# design.net
KiCad netlist of a schematic drawn in Altium Designer
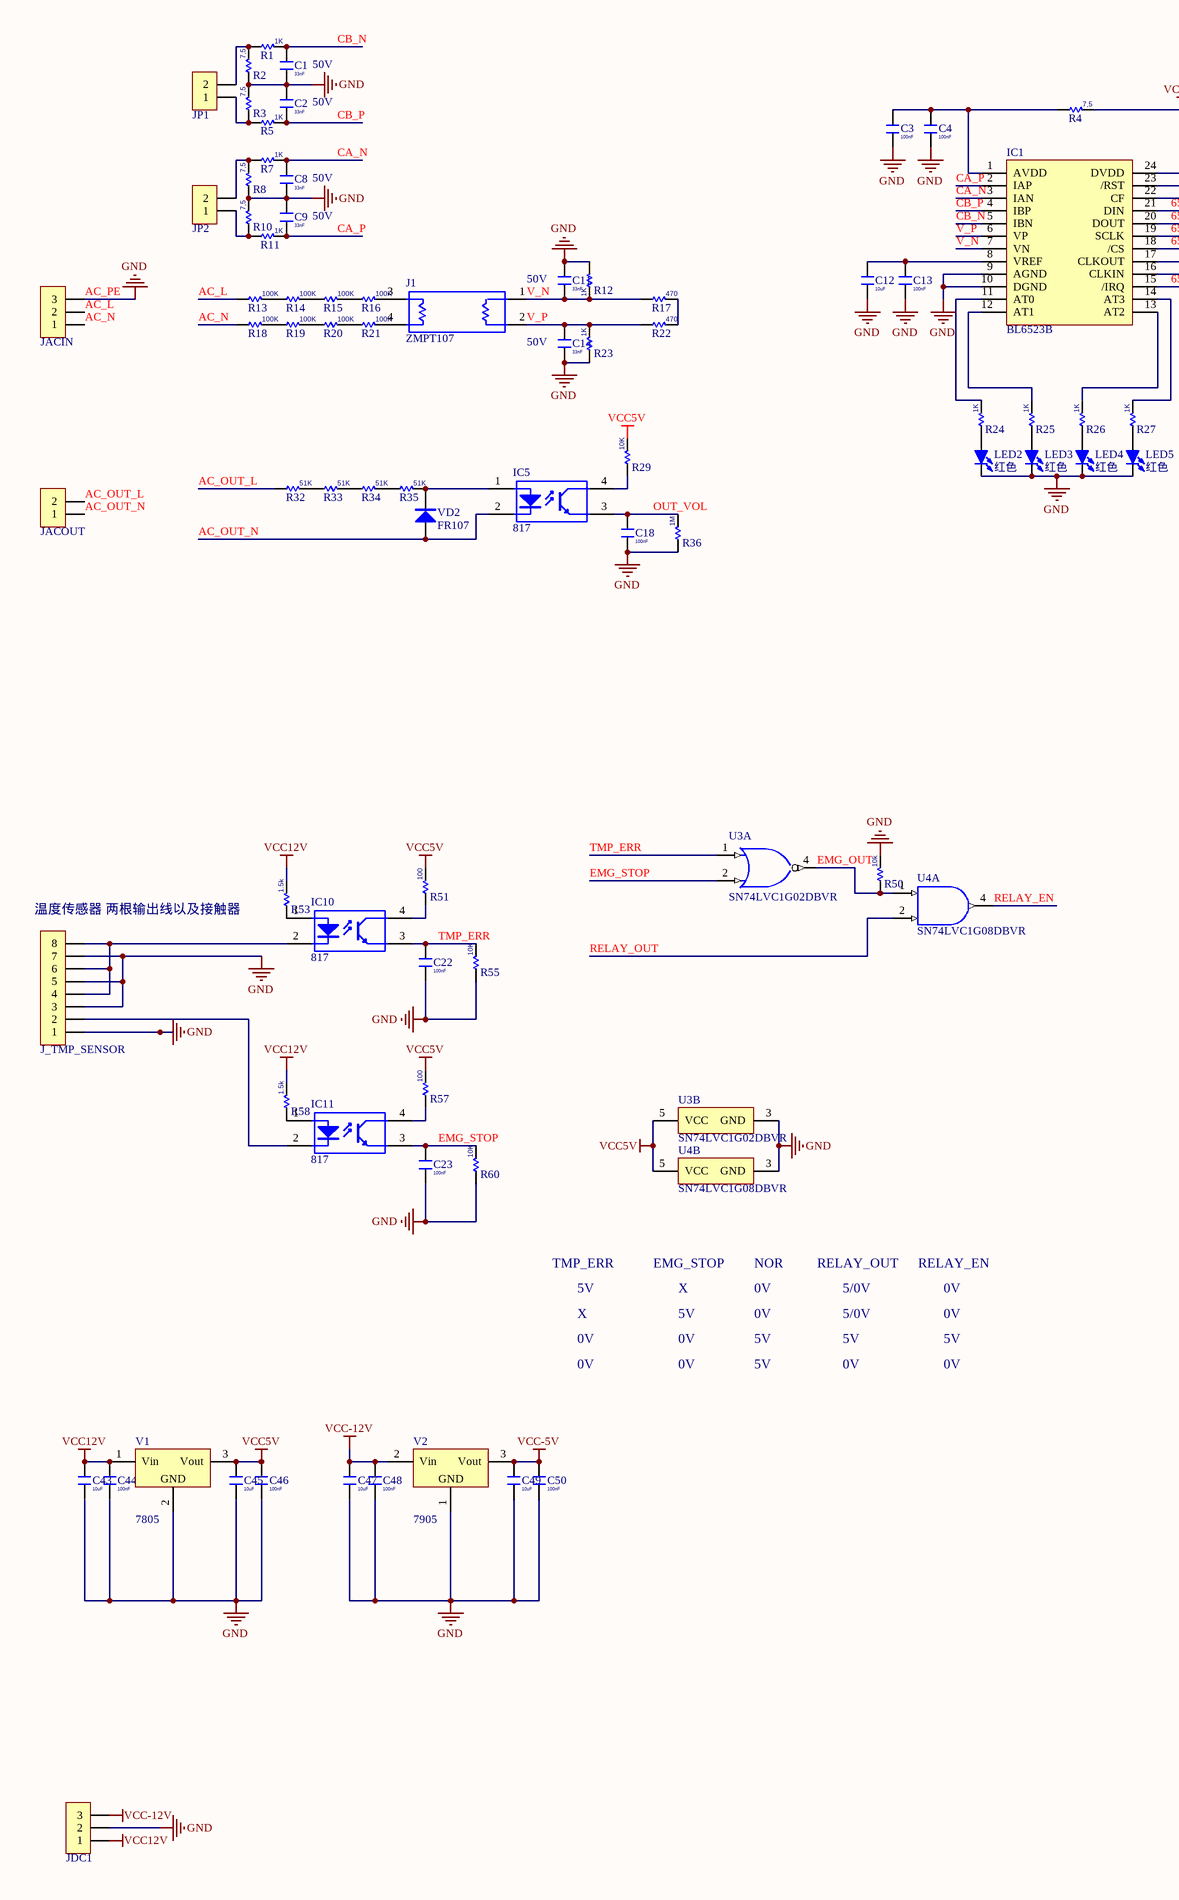
[diagram p0: 计量芯片版本.SchDoc, left]
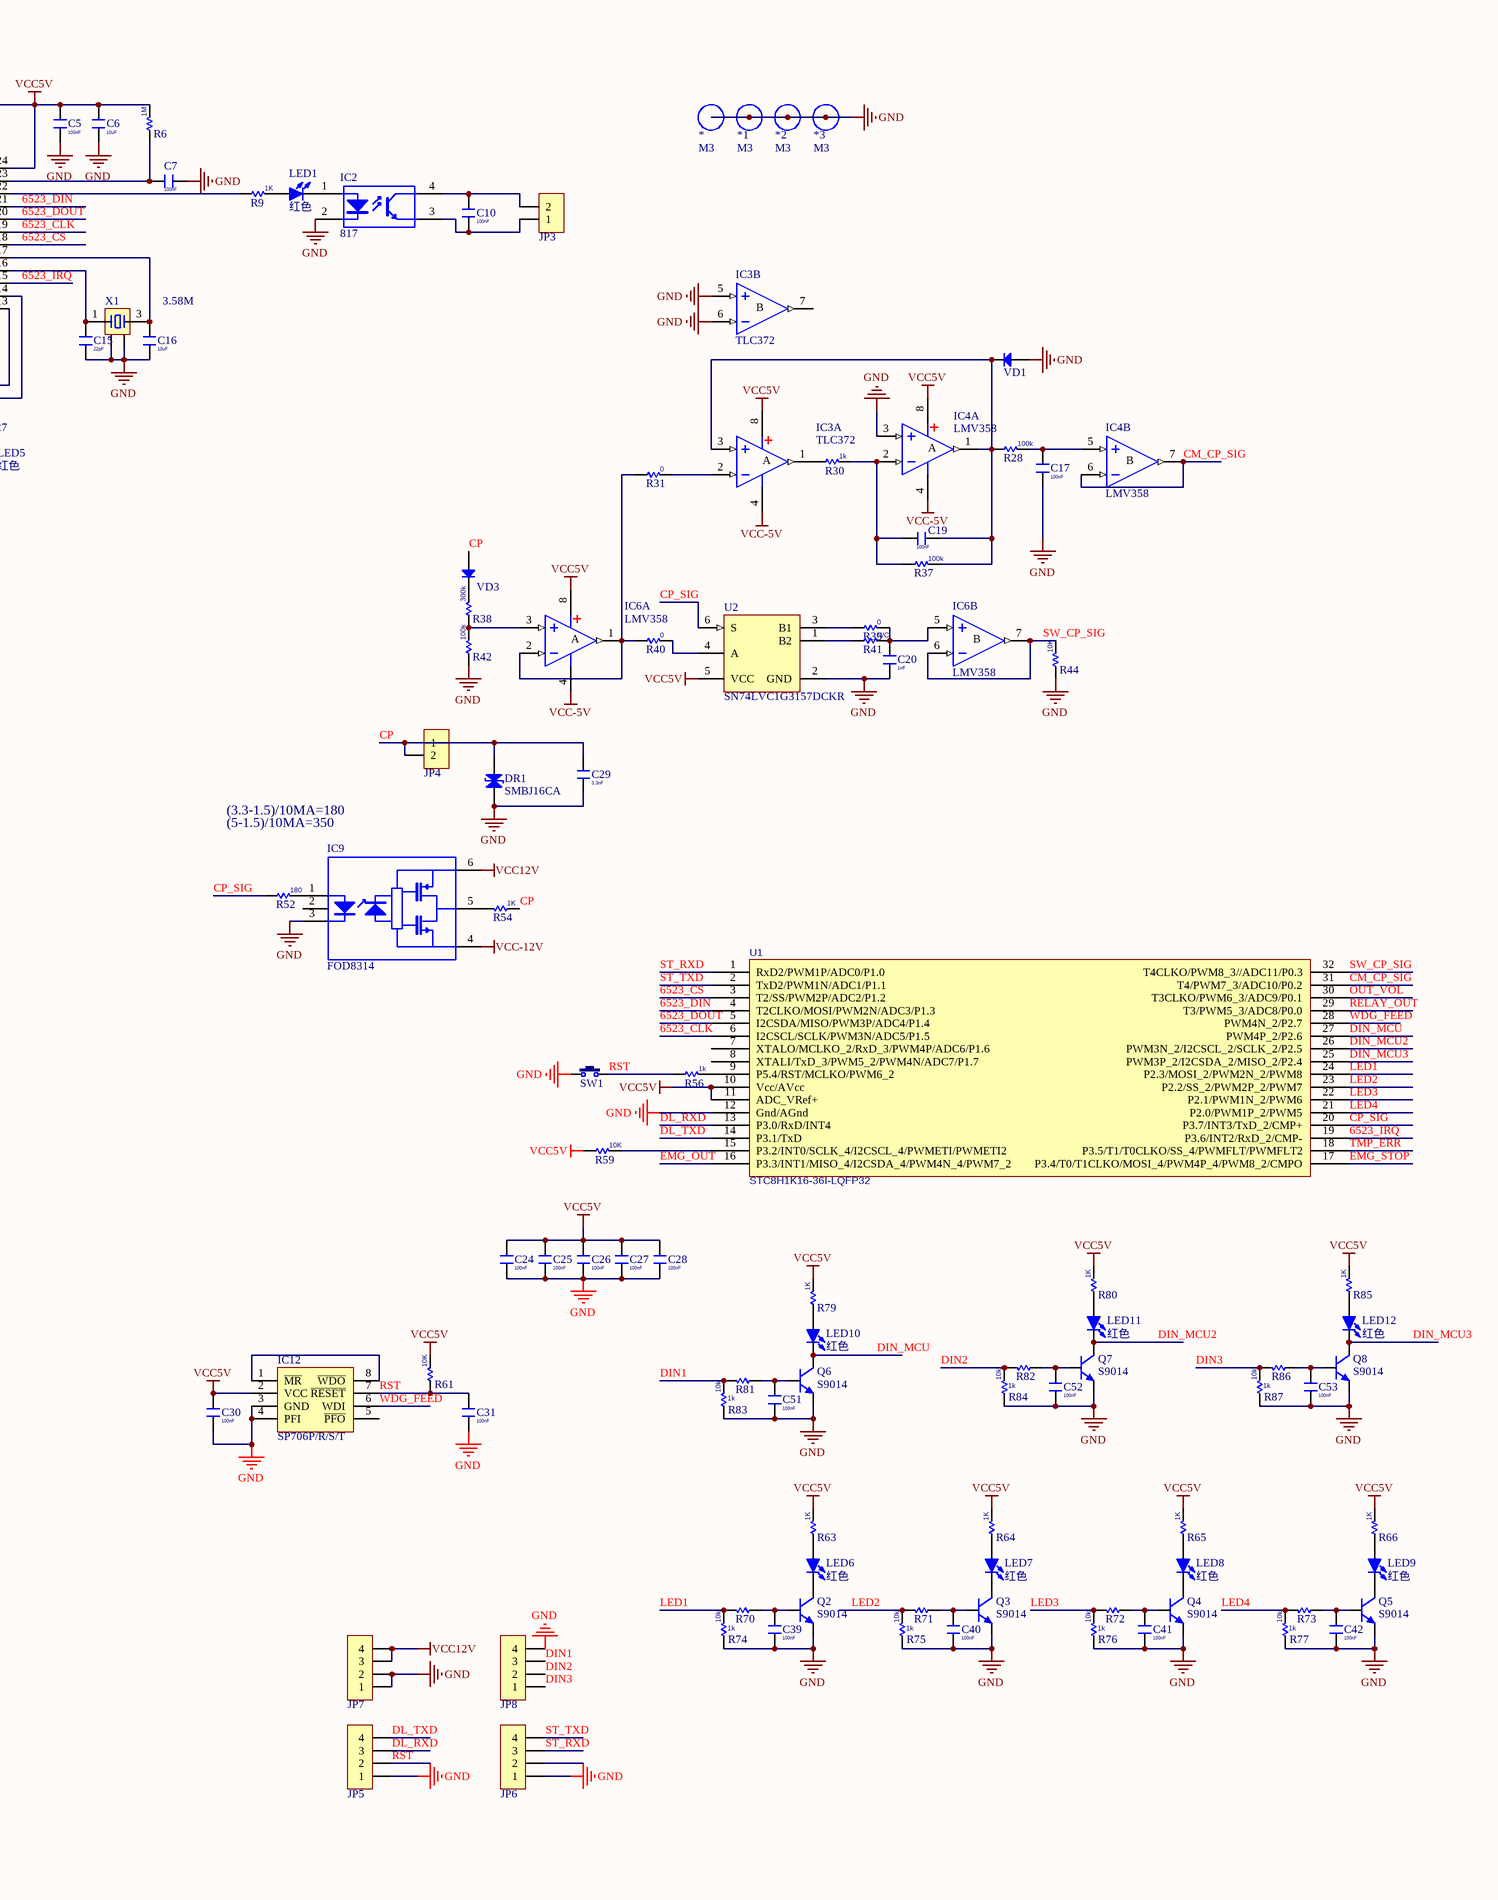
[diagram p1: 计量芯片版本.SchDoc, right]

(export (version "E")
  (design (tool "Eeschema 10.0.6"))
  (components
    (comp (ref "*")
      (value "M3")
      (footprint "M3 125X300")
      (description "铜柱孔")
      (libsource (lib "未分类器件") (part "M3"))
    )
    (comp (ref "*1")
      (value "M3")
      (footprint "M3 125X300")
      (description "铜柱孔")
      (libsource (lib "未分类器件") (part "M3"))
    )
    (comp (ref "*2")
      (value "M3")
      (footprint "M3 125X300")
      (description "铜柱孔")
      (libsource (lib "未分类器件") (part "M3"))
    )
    (comp (ref "*3")
      (value "M3")
      (footprint "M3 125X300")
      (description "铜柱孔")
      (libsource (lib "未分类器件") (part "M3"))
    )
    (comp (ref "C1")
      (value "33nF")
      (footprint "C 0805")
      (description "无极性贴片电容")
      (fields (field (name "VOLTAGE") "50V") (field (name "Comment") "C"))
      (libsource (lib "电阻-电容-电感") (part "C"))
    )
    (comp (ref "C2")
      (value "33nF")
      (footprint "C 0805")
      (description "无极性贴片电容")
      (fields (field (name "VOLTAGE") "50V") (field (name "Comment") "C"))
      (libsource (lib "电阻-电容-电感") (part "C"))
    )
    (comp (ref "C3")
      (value "100nF")
      (footprint "C 0805")
      (description "无极性贴片电容")
      (fields (field (name "VOLTAGE") "20V") (field (name "Comment") "C"))
      (libsource (lib "电阻-电容-电感") (part "C"))
    )
    (comp (ref "C4")
      (value "100nF")
      (footprint "C 0805")
      (description "无极性贴片电容")
      (fields (field (name "VOLTAGE") "20V") (field (name "Comment") "C"))
      (libsource (lib "电阻-电容-电感") (part "C"))
    )
    (comp (ref "C5")
      (value "100nF")
      (footprint "C 0805")
      (description "无极性贴片电容")
      (fields (field (name "VOLTAGE") "20V") (field (name "Comment") "C"))
      (libsource (lib "电阻-电容-电感") (part "C"))
    )
    (comp (ref "C6")
      (value "10uF")
      (footprint "C 0805")
      (description "无极性贴片电容")
      (fields (field (name "VOLTAGE") "20V") (field (name "Comment") "C"))
      (libsource (lib "电阻-电容-电感") (part "C"))
    )
    (comp (ref "C7")
      (value "100nF")
      (footprint "C 0805")
      (description "无极性贴片电容")
      (fields (field (name "VOLTAGE") "20V") (field (name "Comment") "C"))
      (libsource (lib "电阻-电容-电感") (part "C"))
    )
    (comp (ref "C8")
      (value "33nF")
      (footprint "C 0805")
      (description "无极性贴片电容")
      (fields (field (name "VOLTAGE") "50V") (field (name "Comment") "C"))
      (libsource (lib "电阻-电容-电感") (part "C"))
    )
    (comp (ref "C9")
      (value "33nF")
      (footprint "C 0805")
      (description "无极性贴片电容")
      (fields (field (name "VOLTAGE") "50V") (field (name "Comment") "C"))
      (libsource (lib "电阻-电容-电感") (part "C"))
    )
    (comp (ref "C10")
      (value "100nF")
      (footprint "C 0805")
      (description "无极性贴片电容")
      (fields (field (name "VOLTAGE") "20V") (field (name "Comment") "C"))
      (libsource (lib "电阻-电容-电感") (part "C"))
    )
    (comp (ref "C11")
      (value "33nF")
      (footprint "C 0805")
      (description "无极性贴片电容")
      (fields (field (name "VOLTAGE") "50V") (field (name "Comment") "C"))
      (libsource (lib "电阻-电容-电感") (part "C"))
    )
    (comp (ref "C12")
      (value "10uF")
      (footprint "C 0805")
      (description "无极性贴片电容")
      (fields (field (name "VOLTAGE") "20V") (field (name "Comment") "C"))
      (libsource (lib "电阻-电容-电感") (part "C"))
    )
    (comp (ref "C13")
      (value "100nF")
      (footprint "C 0805")
      (description "无极性贴片电容")
      (fields (field (name "VOLTAGE") "20V") (field (name "Comment") "C"))
      (libsource (lib "电阻-电容-电感") (part "C"))
    )
    (comp (ref "C14")
      (value "33nF")
      (footprint "C 0805")
      (description "无极性贴片电容")
      (fields (field (name "VOLTAGE") "50V") (field (name "Comment") "C"))
      (libsource (lib "电阻-电容-电感") (part "C"))
    )
    (comp (ref "C15")
      (value "22pF")
      (footprint "C 0805")
      (description "无极性贴片电容")
      (fields (field (name "VOLTAGE") "20V") (field (name "Comment") "C"))
      (libsource (lib "电阻-电容-电感") (part "C"))
    )
    (comp (ref "C16")
      (value "10uF")
      (footprint "C 0805")
      (description "无极性贴片电容")
      (fields (field (name "VOLTAGE") "20V") (field (name "Comment") "C"))
      (libsource (lib "电阻-电容-电感") (part "C"))
    )
    (comp (ref "C17")
      (value "100nF")
      (footprint "C 0805")
      (description "无极性贴片电容")
      (fields (field (name "VOLTAGE") "20V") (field (name "Comment") "C"))
      (libsource (lib "电阻-电容-电感") (part "C"))
    )
    (comp (ref "C18")
      (value "100nF")
      (footprint "C 0805")
      (description "无极性贴片电容")
      (fields (field (name "VOLTAGE") "20V") (field (name "Comment") "C"))
      (libsource (lib "电阻-电容-电感") (part "C"))
    )
    (comp (ref "C19")
      (value "100nF")
      (footprint "C 0805")
      (description "无极性贴片电容")
      (fields (field (name "VOLTAGE") "20V") (field (name "Comment") "C"))
      (libsource (lib "电阻-电容-电感") (part "C"))
    )
    (comp (ref "C20")
      (value "1nF")
      (footprint "C 0805")
      (description "无极性贴片电容")
      (fields (field (name "VOLTAGE") "20V") (field (name "Comment") "C"))
      (libsource (lib "电阻-电容-电感") (part "C"))
    )
    (comp (ref "C22")
      (value "100nF")
      (footprint "C 0805")
      (description "无极性贴片电容")
      (fields (field (name "VOLTAGE") "20V") (field (name "Comment") "C"))
      (libsource (lib "电阻-电容-电感") (part "C"))
    )
    (comp (ref "C23")
      (value "100nF")
      (footprint "C 0805")
      (description "无极性贴片电容")
      (fields (field (name "VOLTAGE") "20V") (field (name "Comment") "C"))
      (libsource (lib "电阻-电容-电感") (part "C"))
    )
    (comp (ref "C24")
      (value "100nF")
      (footprint "C 0805")
      (description "无极性贴片电容")
      (fields (field (name "VOLTAGE") "20V") (field (name "Comment") "C"))
      (libsource (lib "电阻-电容-电感") (part "C"))
    )
    (comp (ref "C25")
      (value "100nF")
      (footprint "C 0805")
      (description "无极性贴片电容")
      (fields (field (name "VOLTAGE") "20V") (field (name "Comment") "C"))
      (libsource (lib "电阻-电容-电感") (part "C"))
    )
    (comp (ref "C26")
      (value "100nF")
      (footprint "C 0805")
      (description "无极性贴片电容")
      (fields (field (name "VOLTAGE") "20V") (field (name "Comment") "C"))
      (libsource (lib "电阻-电容-电感") (part "C"))
    )
    (comp (ref "C27")
      (value "100nF")
      (footprint "C 0805")
      (description "无极性贴片电容")
      (fields (field (name "VOLTAGE") "20V") (field (name "Comment") "C"))
      (libsource (lib "电阻-电容-电感") (part "C"))
    )
    (comp (ref "C28")
      (value "100nF")
      (footprint "C 0805")
      (description "无极性贴片电容")
      (fields (field (name "VOLTAGE") "20V") (field (name "Comment") "C"))
      (libsource (lib "电阻-电容-电感") (part "C"))
    )
    (comp (ref "C29")
      (value "3.3nF")
      (footprint "C 1206")
      (description "无极性贴片电容")
      (fields (field (name "VOLTAGE") "50V") (field (name "Comment") "C"))
      (libsource (lib "电阻-电容-电感") (part "C"))
    )
    (comp (ref "C30")
      (value "100nF")
      (footprint "C 0805")
      (description "无极性贴片电容")
      (fields (field (name "VOLTAGE") "20V") (field (name "Comment") "C"))
      (libsource (lib "电阻-电容-电感") (part "C"))
    )
    (comp (ref "C31")
      (value "100nF")
      (footprint "C 0805")
      (description "无极性贴片电容")
      (fields (field (name "VOLTAGE") "20V") (field (name "Comment") "C"))
      (libsource (lib "电阻-电容-电感") (part "C"))
    )
    (comp (ref "C39")
      (value "100nF")
      (footprint "C 0805")
      (description "无极性贴片电容")
      (fields (field (name "VOLTAGE") "20V") (field (name "Comment") "C"))
      (libsource (lib "电阻-电容-电感") (part "C"))
    )
    (comp (ref "C40")
      (value "100nF")
      (footprint "C 0805")
      (description "无极性贴片电容")
      (fields (field (name "VOLTAGE") "20V") (field (name "Comment") "C"))
      (libsource (lib "电阻-电容-电感") (part "C"))
    )
    (comp (ref "C41")
      (value "100nF")
      (footprint "C 0805")
      (description "无极性贴片电容")
      (fields (field (name "VOLTAGE") "20V") (field (name "Comment") "C"))
      (libsource (lib "电阻-电容-电感") (part "C"))
    )
    (comp (ref "C42")
      (value "100nF")
      (footprint "C 0805")
      (description "无极性贴片电容")
      (fields (field (name "VOLTAGE") "20V") (field (name "Comment") "C"))
      (libsource (lib "电阻-电容-电感") (part "C"))
    )
    (comp (ref "C43")
      (value "10uF")
      (footprint "C 0805")
      (description "无极性贴片电容")
      (fields (field (name "VOLTAGE") "50V") (field (name "Comment") "C"))
      (libsource (lib "电阻-电容-电感") (part "C"))
    )
    (comp (ref "C44")
      (value "100nF")
      (footprint "C 0805")
      (description "无极性贴片电容")
      (fields (field (name "VOLTAGE") "50V") (field (name "Comment") "C"))
      (libsource (lib "电阻-电容-电感") (part "C"))
    )
    (comp (ref "C45")
      (value "10uF")
      (footprint "C 0805")
      (description "无极性贴片电容")
      (fields (field (name "VOLTAGE") "50V") (field (name "Comment") "C"))
      (libsource (lib "电阻-电容-电感") (part "C"))
    )
    (comp (ref "C46")
      (value "100nF")
      (footprint "C 0805")
      (description "无极性贴片电容")
      (fields (field (name "VOLTAGE") "50V") (field (name "Comment") "C"))
      (libsource (lib "电阻-电容-电感") (part "C"))
    )
    (comp (ref "C47")
      (value "10uF")
      (footprint "C 0805")
      (description "无极性贴片电容")
      (fields (field (name "VOLTAGE") "50V") (field (name "Comment") "C"))
      (libsource (lib "电阻-电容-电感") (part "C"))
    )
    (comp (ref "C48")
      (value "100nF")
      (footprint "C 0805")
      (description "无极性贴片电容")
      (fields (field (name "VOLTAGE") "50V") (field (name "Comment") "C"))
      (libsource (lib "电阻-电容-电感") (part "C"))
    )
    (comp (ref "C49")
      (value "10uF")
      (footprint "C 0805")
      (description "无极性贴片电容")
      (fields (field (name "VOLTAGE") "50V") (field (name "Comment") "C"))
      (libsource (lib "电阻-电容-电感") (part "C"))
    )
    (comp (ref "C50")
      (value "100nF")
      (footprint "C 0805")
      (description "无极性贴片电容")
      (fields (field (name "VOLTAGE") "50V") (field (name "Comment") "C"))
      (libsource (lib "电阻-电容-电感") (part "C"))
    )
    (comp (ref "C51")
      (value "100nF")
      (footprint "C 0805")
      (description "无极性贴片电容")
      (fields (field (name "VOLTAGE") "20V") (field (name "Comment") "C"))
      (libsource (lib "电阻-电容-电感") (part "C"))
    )
    (comp (ref "C52")
      (value "100nF")
      (footprint "C 0805")
      (description "无极性贴片电容")
      (fields (field (name "VOLTAGE") "20V") (field (name "Comment") "C"))
      (libsource (lib "电阻-电容-电感") (part "C"))
    )
    (comp (ref "C53")
      (value "100nF")
      (footprint "C 0805")
      (description "无极性贴片电容")
      (fields (field (name "VOLTAGE") "20V") (field (name "Comment") "C"))
      (libsource (lib "电阻-电容-电感") (part "C"))
    )
    (comp (ref "DR1")
      (value "SMBJ16CA")
      (footprint "SMB")
      (description "瞬态电压抑制二极管")
      (libsource (lib "二极管-整流桥") (part "DR"))
    )
    (comp (ref "IC1")
      (value "BL6523B")
      (footprint "SSOP24_M")
      (description "单相多功能电能计量芯片")
      (libsource (lib "IC芯片") (part "BL6523B"))
    )
    (comp (ref "IC2")
      (value "817")
      (footprint "DIP4-300")
      (description "线性光耦")
      (libsource (lib "传感元件") (part "817"))
    )
    (comp (ref "IC3")
      (value "TLC372")
      (footprint "SOP8_L")
      (description "双路电压比较,MOS下臂输出")
      (libsource (lib "IC芯片") (part "TLC372"))
    )
    (comp (ref "IC4")
      (value "LMV358")
      (footprint "SOP8_N")
      (description "双路运放")
      (libsource (lib "IC芯片") (part "LM358"))
    )
    (comp (ref "IC5")
      (value "817")
      (footprint "DIP4-300")
      (description "线性光耦")
      (libsource (lib "传感元件") (part "817"))
    )
    (comp (ref "IC6")
      (value "LMV358")
      (footprint "SOP8_N")
      (description "双路运放")
      (libsource (lib "IC芯片") (part "LM358"))
    )
    (comp (ref "IC9")
      (value "FOD8314")
      (footprint "SOP6_L")
      (description "MOSFET/IGBT 驱动光耦，15-30v 1a")
      (libsource (lib "传感元件") (part "FOD8314"))
    )
    (comp (ref "IC10")
      (value "817")
      (footprint "DIP4-300")
      (description "线性光耦")
      (libsource (lib "传感元件") (part "817"))
    )
    (comp (ref "IC11")
      (value "817")
      (footprint "DIP4-300")
      (description "线性光耦")
      (libsource (lib "传感元件") (part "817"))
    )
    (comp (ref "IC12")
      (value "SP706P/R/S/T")
      (footprint "SOP8_N")
      (description "处理器监控芯片")
      (libsource (lib "IC芯片") (part "SP706"))
    )
    (comp (ref "J1")
      (value "ZMPT107")
      (footprint "ZMPT107")
      (description "精密电流型电压互感器")
      (libsource (lib "传感元件") (part "ZMPT107"))
    )
    (comp (ref "JACIN")
      (value "HDR-1X3")
      (footprint "KF2EDGK5.0-3P_H")
      (description "3P接插件")
      (libsource (lib "接插件") (part "Header 3"))
    )
    (comp (ref "JACOUT")
      (value "HDR-1X2")
      (footprint "MC 1,5/ 2-G-3,81")
      (description "2P接插件")
      (libsource (lib "") (part "Header 2_2"))
    )
    (comp (ref "JDC1")
      (value "HDR-1X3")
      (footprint "MC 1,5/ 3-G-3,81")
      (description "3P接插件")
      (libsource (lib "接插件") (part "Header 3"))
    )
    (comp (ref "JP1")
      (value "HDR-1X2")
      (footprint "MC 1,5/ 2-G-3,81")
      (description "2P接插件")
      (libsource (lib "") (part "Header 2_2"))
    )
    (comp (ref "JP2")
      (value "HDR-1X2")
      (footprint "MC 1,5/ 2-G-3,81")
      (description "2P接插件")
      (libsource (lib "") (part "Header 2_2"))
    )
    (comp (ref "JP3")
      (value "HDR-1X2")
      (footprint "MC 1,5/ 2-G-3,81")
      (description "2P接插件")
      (libsource (lib "") (part "Header 2_1"))
    )
    (comp (ref "JP4")
      (value "HDR-1X2")
      (footprint "MC 1,5/ 2-G-3,81")
      (description "2P接插件")
      (libsource (lib "接插件") (part "Header 2"))
    )
    (comp (ref "JP5")
      (value "HDR-1X4")
      (footprint "HDR-1X4")
      (description "4P接插件")
      (libsource (lib "接插件") (part "Header 4"))
    )
    (comp (ref "JP6")
      (value "HDR-1X4")
      (footprint "MC 1,5/ 4-G-3,81")
      (description "4P接插件")
      (libsource (lib "接插件") (part "Header 4"))
    )
    (comp (ref "JP7")
      (value "HDR-1X4")
      (footprint "MC 1,5/ 4-G-3,81")
      (description "4P接插件")
      (libsource (lib "接插件") (part "Header 4"))
    )
    (comp (ref "JP8")
      (value "HDR-1X4")
      (footprint "MC 1,5/ 4-G-3,81")
      (description "4P接插件")
      (libsource (lib "接插件") (part "Header 4"))
    )
    (comp (ref "J_TMP_SENSOR")
      (value "HDR-1X8")
      (footprint "MC 1,5/ 8-G-3,81")
      (description "8P接插件")
      (libsource (lib "接插件") (part "Header 8"))
    )
    (comp (ref "LED1")
      (value "红色")
      (footprint "LED 0805G")
      (description "贴片LED")
      (libsource (lib "LED") (part "LED-SMD"))
    )
    (comp (ref "LED2")
      (value "红色")
      (footprint "LED 0805G")
      (description "贴片LED")
      (libsource (lib "LED") (part "LED-SMD"))
    )
    (comp (ref "LED3")
      (value "红色")
      (footprint "LED 0805G")
      (description "贴片LED")
      (libsource (lib "LED") (part "LED-SMD"))
    )
    (comp (ref "LED4")
      (value "红色")
      (footprint "LED 0805G")
      (description "贴片LED")
      (libsource (lib "LED") (part "LED-SMD"))
    )
    (comp (ref "LED5")
      (value "红色")
      (footprint "LED 0805G")
      (description "贴片LED")
      (libsource (lib "LED") (part "LED-SMD"))
    )
    (comp (ref "LED6")
      (value "红色")
      (footprint "LED 0805G")
      (description "贴片LED")
      (libsource (lib "LED") (part "LED-SMD"))
    )
    (comp (ref "LED7")
      (value "红色")
      (footprint "LED 0805G")
      (description "贴片LED")
      (libsource (lib "LED") (part "LED-SMD"))
    )
    (comp (ref "LED8")
      (value "红色")
      (footprint "LED 0805G")
      (description "贴片LED")
      (libsource (lib "LED") (part "LED-SMD"))
    )
    (comp (ref "LED9")
      (value "红色")
      (footprint "LED 0805G")
      (description "贴片LED")
      (libsource (lib "LED") (part "LED-SMD"))
    )
    (comp (ref "LED10")
      (value "红色")
      (footprint "LED 0805G")
      (description "贴片LED")
      (libsource (lib "LED") (part "LED-SMD"))
    )
    (comp (ref "LED11")
      (value "红色")
      (footprint "LED 0805G")
      (description "贴片LED")
      (libsource (lib "LED") (part "LED-SMD"))
    )
    (comp (ref "LED12")
      (value "红色")
      (footprint "LED 0805G")
      (description "贴片LED")
      (libsource (lib "LED") (part "LED-SMD"))
    )
    (comp (ref "Q2")
      (value "S9014")
      (footprint "SOT23-3N")
      (description "低噪放大-NPN型")
      (libsource (lib "三极管") (part "9014-SMD"))
    )
    (comp (ref "Q3")
      (value "S9014")
      (footprint "SOT23-3N")
      (description "低噪放大-NPN型")
      (libsource (lib "三极管") (part "9014-SMD"))
    )
    (comp (ref "Q4")
      (value "S9014")
      (footprint "SOT23-3N")
      (description "低噪放大-NPN型")
      (libsource (lib "三极管") (part "9014-SMD"))
    )
    (comp (ref "Q5")
      (value "S9014")
      (footprint "SOT23-3N")
      (description "低噪放大-NPN型")
      (libsource (lib "三极管") (part "9014-SMD"))
    )
    (comp (ref "Q6")
      (value "S9014")
      (footprint "SOT23-3N")
      (description "低噪放大-NPN型")
      (libsource (lib "三极管") (part "9014-SMD"))
    )
    (comp (ref "Q7")
      (value "S9014")
      (footprint "SOT23-3N")
      (description "低噪放大-NPN型")
      (libsource (lib "三极管") (part "9014-SMD"))
    )
    (comp (ref "Q8")
      (value "S9014")
      (footprint "SOT23-3N")
      (description "低噪放大-NPN型")
      (libsource (lib "三极管") (part "9014-SMD"))
    )
    (comp (ref "R1")
      (value "1K")
      (footprint "R 0805")
      (description "贴片电阻")
      (fields (field (name "Comment") "R"))
      (libsource (lib "电阻-电容-电感") (part "R"))
    )
    (comp (ref "R2")
      (value "7,5")
      (footprint "R 0805")
      (description "贴片电阻")
      (fields (field (name "Comment") "R"))
      (libsource (lib "电阻-电容-电感") (part "R"))
    )
    (comp (ref "R3")
      (value "7,5")
      (footprint "R 0805")
      (description "贴片电阻")
      (fields (field (name "Comment") "R"))
      (libsource (lib "电阻-电容-电感") (part "R"))
    )
    (comp (ref "R4")
      (value "7,5")
      (footprint "R 0805")
      (description "贴片电阻")
      (fields (field (name "Comment") "R"))
      (libsource (lib "电阻-电容-电感") (part "R"))
    )
    (comp (ref "R5")
      (value "1K")
      (footprint "R 0805")
      (description "贴片电阻")
      (fields (field (name "Comment") "R"))
      (libsource (lib "电阻-电容-电感") (part "R"))
    )
    (comp (ref "R6")
      (value "1M")
      (footprint "R 0805")
      (description "贴片电阻")
      (fields (field (name "Comment") "R"))
      (libsource (lib "电阻-电容-电感") (part "R"))
    )
    (comp (ref "R7")
      (value "1K")
      (footprint "R 0805")
      (description "贴片电阻")
      (fields (field (name "Comment") "R"))
      (libsource (lib "电阻-电容-电感") (part "R"))
    )
    (comp (ref "R8")
      (value "7,5")
      (footprint "R 0805")
      (description "贴片电阻")
      (fields (field (name "Comment") "R"))
      (libsource (lib "电阻-电容-电感") (part "R"))
    )
    (comp (ref "R9")
      (value "1K")
      (footprint "R 0805")
      (description "贴片电阻")
      (fields (field (name "Comment") "R"))
      (libsource (lib "电阻-电容-电感") (part "R"))
    )
    (comp (ref "R10")
      (value "7,5")
      (footprint "R 0805")
      (description "贴片电阻")
      (fields (field (name "Comment") "R"))
      (libsource (lib "电阻-电容-电感") (part "R"))
    )
    (comp (ref "R11")
      (value "1K")
      (footprint "R 0805")
      (description "贴片电阻")
      (fields (field (name "Comment") "R"))
      (libsource (lib "电阻-电容-电感") (part "R"))
    )
    (comp (ref "R12")
      (value "1K")
      (footprint "R 0805")
      (description "贴片电阻")
      (fields (field (name "Comment") "R"))
      (libsource (lib "电阻-电容-电感") (part "R"))
    )
    (comp (ref "R13")
      (value "100K")
      (footprint "R 1206")
      (description "贴片电阻")
      (fields (field (name "Comment") "R"))
      (libsource (lib "电阻-电容-电感") (part "R"))
    )
    (comp (ref "R14")
      (value "100K")
      (footprint "R 1206")
      (description "贴片电阻")
      (fields (field (name "Comment") "R"))
      (libsource (lib "电阻-电容-电感") (part "R"))
    )
    (comp (ref "R15")
      (value "100K")
      (footprint "R 1206")
      (description "贴片电阻")
      (fields (field (name "Comment") "R"))
      (libsource (lib "电阻-电容-电感") (part "R"))
    )
    (comp (ref "R16")
      (value "100K")
      (footprint "R 1206")
      (description "贴片电阻")
      (fields (field (name "Comment") "R"))
      (libsource (lib "电阻-电容-电感") (part "R"))
    )
    (comp (ref "R17")
      (value "470")
      (footprint "R 0805")
      (description "贴片电阻")
      (fields (field (name "Comment") "R"))
      (libsource (lib "电阻-电容-电感") (part "R"))
    )
    (comp (ref "R18")
      (value "100K")
      (footprint "R 1206")
      (description "贴片电阻")
      (fields (field (name "Comment") "R"))
      (libsource (lib "电阻-电容-电感") (part "R"))
    )
    (comp (ref "R19")
      (value "100K")
      (footprint "R 1206")
      (description "贴片电阻")
      (fields (field (name "Comment") "R"))
      (libsource (lib "电阻-电容-电感") (part "R"))
    )
    (comp (ref "R20")
      (value "100K")
      (footprint "R 1206")
      (description "贴片电阻")
      (fields (field (name "Comment") "R"))
      (libsource (lib "电阻-电容-电感") (part "R"))
    )
    (comp (ref "R21")
      (value "100K")
      (footprint "R 1206")
      (description "贴片电阻")
      (fields (field (name "Comment") "R"))
      (libsource (lib "电阻-电容-电感") (part "R"))
    )
    (comp (ref "R22")
      (value "470")
      (footprint "R 0805")
      (description "贴片电阻")
      (fields (field (name "Comment") "R"))
      (libsource (lib "电阻-电容-电感") (part "R"))
    )
    (comp (ref "R23")
      (value "1K")
      (footprint "R 0805")
      (description "贴片电阻")
      (fields (field (name "Comment") "R"))
      (libsource (lib "电阻-电容-电感") (part "R"))
    )
    (comp (ref "R24")
      (value "1K")
      (footprint "R 0805")
      (description "贴片电阻")
      (fields (field (name "Comment") "R"))
      (libsource (lib "电阻-电容-电感") (part "R"))
    )
    (comp (ref "R25")
      (value "1K")
      (footprint "R 0805")
      (description "贴片电阻")
      (fields (field (name "Comment") "R"))
      (libsource (lib "电阻-电容-电感") (part "R"))
    )
    (comp (ref "R26")
      (value "1K")
      (footprint "R 0805")
      (description "贴片电阻")
      (fields (field (name "Comment") "R"))
      (libsource (lib "电阻-电容-电感") (part "R"))
    )
    (comp (ref "R27")
      (value "1K")
      (footprint "R 0805")
      (description "贴片电阻")
      (fields (field (name "Comment") "R"))
      (libsource (lib "电阻-电容-电感") (part "R"))
    )
    (comp (ref "R28")
      (value "100k")
      (footprint "R 0805")
      (description "贴片电阻")
      (fields (field (name "Comment") "R"))
      (libsource (lib "电阻-电容-电感") (part "R"))
    )
    (comp (ref "R29")
      (value "10K")
      (footprint "R 0805")
      (description "贴片电阻")
      (fields (field (name "Comment") "R"))
      (libsource (lib "电阻-电容-电感") (part "R"))
    )
    (comp (ref "R30")
      (value "1k")
      (footprint "R 0805")
      (description "贴片电阻")
      (fields (field (name "Comment") "R"))
      (libsource (lib "电阻-电容-电感") (part "R"))
    )
    (comp (ref "R31")
      (value "0")
      (footprint "R 0805")
      (description "贴片电阻")
      (fields (field (name "Comment") "R"))
      (libsource (lib "电阻-电容-电感") (part "R"))
    )
    (comp (ref "R32")
      (value "51K")
      (footprint "R 1206")
      (description "贴片电阻")
      (fields (field (name "Comment") "R"))
      (libsource (lib "电阻-电容-电感") (part "R"))
    )
    (comp (ref "R33")
      (value "51K")
      (footprint "R 1206")
      (description "贴片电阻")
      (fields (field (name "Comment") "R"))
      (libsource (lib "电阻-电容-电感") (part "R"))
    )
    (comp (ref "R34")
      (value "51K")
      (footprint "R 1206")
      (description "贴片电阻")
      (fields (field (name "Comment") "R"))
      (libsource (lib "电阻-电容-电感") (part "R"))
    )
    (comp (ref "R35")
      (value "51K")
      (footprint "R 1206")
      (description "贴片电阻")
      (fields (field (name "Comment") "R"))
      (libsource (lib "电阻-电容-电感") (part "R"))
    )
    (comp (ref "R36")
      (value "1M")
      (footprint "R 0805")
      (description "贴片电阻")
      (fields (field (name "Comment") "R"))
      (libsource (lib "电阻-电容-电感") (part "R"))
    )
    (comp (ref "R37")
      (value "100k")
      (footprint "R 0805")
      (description "贴片电阻")
      (fields (field (name "Comment") "R"))
      (libsource (lib "电阻-电容-电感") (part "R"))
    )
    (comp (ref "R38")
      (value "300k")
      (footprint "R 0805")
      (description "贴片电阻")
      (fields (field (name "Comment") "R"))
      (libsource (lib "电阻-电容-电感") (part "R"))
    )
    (comp (ref "R39")
      (value "0")
      (footprint "R 0805")
      (description "贴片电阻")
      (fields (field (name "Comment") "R"))
      (libsource (lib "电阻-电容-电感") (part "R"))
    )
    (comp (ref "R40")
      (value "0")
      (footprint "R 0805")
      (description "贴片电阻")
      (fields (field (name "Comment") "R"))
      (libsource (lib "电阻-电容-电感") (part "R"))
    )
    (comp (ref "R41")
      (value "N/C")
      (footprint "R 0805")
      (description "贴片电阻")
      (fields (field (name "Comment") "R"))
      (libsource (lib "电阻-电容-电感") (part "R"))
    )
    (comp (ref "R42")
      (value "100k")
      (footprint "R 0805")
      (description "贴片电阻")
      (fields (field (name "Comment") "R"))
      (libsource (lib "电阻-电容-电感") (part "R"))
    )
    (comp (ref "R44")
      (value "10K")
      (footprint "R 0805")
      (description "贴片电阻")
      (fields (field (name "Comment") "R"))
      (libsource (lib "电阻-电容-电感") (part "R"))
    )
    (comp (ref "R50")
      (value "10k")
      (footprint "R 0805")
      (description "贴片电阻")
      (fields (field (name "Comment") "R"))
      (libsource (lib "电阻-电容-电感") (part "R"))
    )
    (comp (ref "R51")
      (value "100")
      (footprint "R 0805")
      (description "贴片电阻")
      (fields (field (name "Comment") "R"))
      (libsource (lib "电阻-电容-电感") (part "R"))
    )
    (comp (ref "R52")
      (value "180")
      (footprint "R 0805")
      (description "贴片电阻")
      (fields (field (name "Comment") "R"))
      (libsource (lib "电阻-电容-电感") (part "R"))
    )
    (comp (ref "R53")
      (value "1.5k")
      (footprint "R 0805")
      (description "贴片电阻")
      (fields (field (name "Comment") "R"))
      (libsource (lib "电阻-电容-电感") (part "R"))
    )
    (comp (ref "R54")
      (value "1K")
      (footprint "R 1206")
      (description "贴片电阻")
      (fields (field (name "Comment") "R"))
      (libsource (lib "电阻-电容-电感") (part "R"))
    )
    (comp (ref "R55")
      (value "10K")
      (footprint "R 0805")
      (description "贴片电阻")
      (fields (field (name "Comment") "R"))
      (libsource (lib "电阻-电容-电感") (part "R"))
    )
    (comp (ref "R56")
      (value "1k")
      (footprint "R 0805")
      (description "贴片电阻")
      (fields (field (name "Comment") "R"))
      (libsource (lib "电阻-电容-电感") (part "R"))
    )
    (comp (ref "R57")
      (value "100")
      (footprint "R 0805")
      (description "贴片电阻")
      (fields (field (name "Comment") "R"))
      (libsource (lib "电阻-电容-电感") (part "R"))
    )
    (comp (ref "R58")
      (value "1.5k")
      (footprint "R 0805")
      (description "贴片电阻")
      (fields (field (name "Comment") "R"))
      (libsource (lib "电阻-电容-电感") (part "R"))
    )
    (comp (ref "R59")
      (value "10K")
      (footprint "R 0805")
      (description "贴片电阻")
      (fields (field (name "Comment") "R"))
      (libsource (lib "电阻-电容-电感") (part "R"))
    )
    (comp (ref "R60")
      (value "10K")
      (footprint "R 0805")
      (description "贴片电阻")
      (fields (field (name "Comment") "R"))
      (libsource (lib "电阻-电容-电感") (part "R"))
    )
    (comp (ref "R61")
      (value "10K")
      (footprint "R 0805")
      (description "贴片电阻")
      (fields (field (name "Comment") "R"))
      (libsource (lib "电阻-电容-电感") (part "R"))
    )
    (comp (ref "R63")
      (value "1K")
      (footprint "R 0805")
      (description "贴片电阻")
      (fields (field (name "Comment") "R"))
      (libsource (lib "电阻-电容-电感") (part "R"))
    )
    (comp (ref "R64")
      (value "1K")
      (footprint "R 0805")
      (description "贴片电阻")
      (fields (field (name "Comment") "R"))
      (libsource (lib "电阻-电容-电感") (part "R"))
    )
    (comp (ref "R65")
      (value "1K")
      (footprint "R 0805")
      (description "贴片电阻")
      (fields (field (name "Comment") "R"))
      (libsource (lib "电阻-电容-电感") (part "R"))
    )
    (comp (ref "R66")
      (value "1K")
      (footprint "R 0805")
      (description "贴片电阻")
      (fields (field (name "Comment") "R"))
      (libsource (lib "电阻-电容-电感") (part "R"))
    )
    (comp (ref "R70")
      (value "1k")
      (footprint "R 0805")
      (description "贴片电阻")
      (fields (field (name "Comment") "R"))
      (libsource (lib "电阻-电容-电感") (part "R"))
    )
    (comp (ref "R71")
      (value "1k")
      (footprint "R 0805")
      (description "贴片电阻")
      (fields (field (name "Comment") "R"))
      (libsource (lib "电阻-电容-电感") (part "R"))
    )
    (comp (ref "R72")
      (value "1k")
      (footprint "R 0805")
      (description "贴片电阻")
      (fields (field (name "Comment") "R"))
      (libsource (lib "电阻-电容-电感") (part "R"))
    )
    (comp (ref "R73")
      (value "1k")
      (footprint "R 0805")
      (description "贴片电阻")
      (fields (field (name "Comment") "R"))
      (libsource (lib "电阻-电容-电感") (part "R"))
    )
    (comp (ref "R74")
      (value "10k")
      (footprint "R 0805")
      (description "贴片电阻")
      (fields (field (name "Comment") "R"))
      (libsource (lib "电阻-电容-电感") (part "R"))
    )
    (comp (ref "R75")
      (value "10k")
      (footprint "R 0805")
      (description "贴片电阻")
      (fields (field (name "Comment") "R"))
      (libsource (lib "电阻-电容-电感") (part "R"))
    )
    (comp (ref "R76")
      (value "10k")
      (footprint "R 0805")
      (description "贴片电阻")
      (fields (field (name "Comment") "R"))
      (libsource (lib "电阻-电容-电感") (part "R"))
    )
    (comp (ref "R77")
      (value "10k")
      (footprint "R 0805")
      (description "贴片电阻")
      (fields (field (name "Comment") "R"))
      (libsource (lib "电阻-电容-电感") (part "R"))
    )
    (comp (ref "R79")
      (value "1K")
      (footprint "R 0805")
      (description "贴片电阻")
      (fields (field (name "Comment") "R"))
      (libsource (lib "电阻-电容-电感") (part "R"))
    )
    (comp (ref "R80")
      (value "1K")
      (footprint "R 0805")
      (description "贴片电阻")
      (fields (field (name "Comment") "R"))
      (libsource (lib "电阻-电容-电感") (part "R"))
    )
    (comp (ref "R81")
      (value "1k")
      (footprint "R 0805")
      (description "贴片电阻")
      (fields (field (name "Comment") "R"))
      (libsource (lib "电阻-电容-电感") (part "R"))
    )
    (comp (ref "R82")
      (value "1k")
      (footprint "R 0805")
      (description "贴片电阻")
      (fields (field (name "Comment") "R"))
      (libsource (lib "电阻-电容-电感") (part "R"))
    )
    (comp (ref "R83")
      (value "10k")
      (footprint "R 0805")
      (description "贴片电阻")
      (fields (field (name "Comment") "R"))
      (libsource (lib "电阻-电容-电感") (part "R"))
    )
    (comp (ref "R84")
      (value "10k")
      (footprint "R 0805")
      (description "贴片电阻")
      (fields (field (name "Comment") "R"))
      (libsource (lib "电阻-电容-电感") (part "R"))
    )
    (comp (ref "R85")
      (value "1K")
      (footprint "R 0805")
      (description "贴片电阻")
      (fields (field (name "Comment") "R"))
      (libsource (lib "电阻-电容-电感") (part "R"))
    )
    (comp (ref "R86")
      (value "1k")
      (footprint "R 0805")
      (description "贴片电阻")
      (fields (field (name "Comment") "R"))
      (libsource (lib "电阻-电容-电感") (part "R"))
    )
    (comp (ref "R87")
      (value "10k")
      (footprint "R 0805")
      (description "贴片电阻")
      (fields (field (name "Comment") "R"))
      (libsource (lib "电阻-电容-电感") (part "R"))
    )
    (comp (ref "SW1") (value "NC") (footprint "HDR-1x2") (libsource (lib "按键-开关") (part "TSW 3x6")))
    (comp (ref "U1")
      (value "STC8H1K16-36I-LQFP32")
      (footprint "LQFP32 7X7_N")
      (libsource (lib "STC系列单片机") (part "STC8H1K16-36I-LQFP32"))
    )
    (comp (ref "U2")
      (value "SN74LVC1G3157DCKR")
      (footprint "DCK0006A_N")
      (description "Single-Pole, Double-Throw Analog Switch, DCK0006A, LARGE T&R")
      (fields
        (field (name "GENERIC PART NUMBER") "SN74LVC1G3157")
        (field (name "MANUFACTURER") "Texas Instruments")
      )
      (libsource (lib "TI_Logic_Little_Logic") (part "SN74LVC1G3157DCKR"))
    )
    (comp (ref "U3")
      (value "SN74LVC1G02DBVR")
      (footprint "DBV0005A_N")
      (description "Single 2-Input Positive-NOR Gate, DBV0005A, LARGE T&R")
      (fields
        (field (name "GENERIC PART NUMBER") "SN74LVC1G02")
        (field (name "MANUFACTURER") "Texas Instruments")
      )
      (libsource (lib "TI_Logic_Little_Logic") (part "SN74LVC1G02DBVR"))
    )
    (comp (ref "U4")
      (value "SN74LVC1G08DBVR")
      (footprint "DBV0005A_N")
      (description "Single 2-Input Positive-AND Gate, DBV0005A, LARGE T&R")
      (fields
        (field (name "GENERIC PART NUMBER") "SN74LVC1G08")
        (field (name "MANUFACTURER") "Texas Instruments")
      )
      (libsource (lib "TI_Logic_Little_Logic") (part "SN74LVC1G08DBVR"))
    )
    (comp (ref "V1")
      (value "7805")
      (footprint "TO252")
      (description "线性稳压芯片")
      (libsource (lib "IC芯片") (part "78xx"))
    )
    (comp (ref "V2")
      (value "7905")
      (footprint "TO252")
      (description "线性稳压芯片")
      (libsource (lib "IC芯片") (part "79xx"))
    )
    (comp (ref "VD1")
      (value "1N4148")
      (footprint "SOD-323")
      (description "高速开关二极管")
      (libsource (lib "二极管-整流桥") (part "1N4148"))
    )
    (comp (ref "VD2")
      (value "FR107")
      (footprint "SOD-123")
      (description "快恢复整流二极管")
      (libsource (lib "二极管-整流桥") (part "FR107"))
    )
    (comp (ref "VD3")
      (value "1N4148")
      (footprint "SOD-323")
      (description "高速开关二极管")
      (libsource (lib "二极管-整流桥") (part "1N4148"))
    )
    (comp (ref "X1")
      (value "3.58M")
      (footprint "XTAL-3225")
      (description "4脚晶振")
      (libsource (lib "保险丝-晶振") (part "XTAL-4"))
    )
  )
  (nets
    (net (code "1") (name "/6523_CLK") (class "Default")
      (node (ref "IC1") (pin "19") (pinfunction "SCLK_19") (pintype "passive"))
      (node (ref "U1") (pin "6") (pinfunction "I2CSCL/SCLK/PWM3N/ADC5/P1.5_6") (pintype "passive"))
    )
    (net (code "2") (name "/6523_CS") (class "Default")
      (node (ref "IC1") (pin "18") (pinfunction "/CS_18") (pintype "passive"))
      (node (ref "U1") (pin "3") (pinfunction "T2/SS/PWM2P/ADC2/P1.2_3") (pintype "passive"))
    )
    (net (code "3") (name "/6523_DIN") (class "Default")
      (node (ref "IC1") (pin "21") (pinfunction "DIN_21") (pintype "passive"))
      (node (ref "U1") (pin "4") (pinfunction "T2CLKO/MOSI/PWM2N/ADC3/P1.3_4") (pintype "passive"))
    )
    (net (code "4") (name "/6523_DOUT") (class "Default")
      (node (ref "IC1") (pin "20") (pinfunction "DOUT_20") (pintype "passive"))
      (node (ref "U1") (pin "5") (pinfunction "I2CSDA/MISO/PWM3P/ADC4/P1.4_5") (pintype "passive"))
    )
    (net (code "5") (name "/6523_IRQ") (class "Default")
      (node (ref "IC1") (pin "15") (pinfunction "/IRQ_15") (pintype "passive"))
      (node (ref "U1") (pin "19") (pinfunction "P3.6/INT2/RxD_2/CMP-_19") (pintype "passive"))
    )
    (net (code "6") (name "/AC_L") (class "Default")
      (node (ref "JACIN") (pin "2") (pinfunction "2_2") (pintype "passive"))
      (node (ref "R13") (pin "1") (pinfunction "1_1") (pintype "passive"))
    )
    (net (code "7") (name "/AC_N") (class "Default")
      (node (ref "JACIN") (pin "1") (pinfunction "1_1") (pintype "passive"))
      (node (ref "R18") (pin "1") (pinfunction "1_1") (pintype "passive"))
    )
    (net (code "8") (name "/AC_OUT_L") (class "Default")
      (node (ref "JACOUT") (pin "2") (pinfunction "2_2") (pintype "passive"))
      (node (ref "R32") (pin "1") (pinfunction "1_1") (pintype "passive"))
    )
    (net (code "9") (name "/AC_OUT_N") (class "Default")
      (node (ref "IC5") (pin "2") (pinfunction "K_2") (pintype "passive"))
      (node (ref "JACOUT") (pin "1") (pinfunction "1_1") (pintype "passive"))
      (node (ref "VD2") (pin "1") (pinfunction "A_1") (pintype "passive"))
    )
    (net (code "10") (name "/CA_N") (class "Default")
      (node (ref "C8") (pin "2") (pinfunction "2_2") (pintype "passive"))
      (node (ref "IC1") (pin "3") (pinfunction "IAN_3") (pintype "passive"))
      (node (ref "R7") (pin "2") (pinfunction "2_2") (pintype "passive"))
    )
    (net (code "11") (name "/CA_P") (class "Default")
      (node (ref "C9") (pin "1") (pinfunction "1_1") (pintype "passive"))
      (node (ref "IC1") (pin "2") (pinfunction "IAP_2") (pintype "passive"))
      (node (ref "R11") (pin "2") (pinfunction "2_2") (pintype "passive"))
    )
    (net (code "12") (name "/CB_N") (class "Default")
      (node (ref "C1") (pin "2") (pinfunction "2_2") (pintype "passive"))
      (node (ref "IC1") (pin "5") (pinfunction "IBN_5") (pintype "passive"))
      (node (ref "R1") (pin "2") (pinfunction "2_2") (pintype "passive"))
    )
    (net (code "13") (name "/CB_P") (class "Default")
      (node (ref "C2") (pin "1") (pinfunction "1_1") (pintype "passive"))
      (node (ref "IC1") (pin "4") (pinfunction "IBP_4") (pintype "passive"))
      (node (ref "R5") (pin "2") (pinfunction "2_2") (pintype "passive"))
    )
    (net (code "14") (name "/CM_CP_SIG") (class "Default")
      (node (ref "IC4") (pin "6") (pinfunction "IN-_6") (pintype "input"))
      (node (ref "IC4") (pin "7") (pinfunction "OUT_7") (pintype "output"))
      (node (ref "U1") (pin "31") (pinfunction "T4/PWM7_3/ADC10/P0.2_31") (pintype "passive"))
    )
    (net (code "15") (name "/CP") (class "Default")
      (node (ref "C29") (pin "2") (pinfunction "2_2") (pintype "passive"))
      (node (ref "DR1") (pin "1") (pinfunction "A_1") (pintype "passive"))
      (node (ref "JP4") (pin "1") (pinfunction "1_1") (pintype "passive"))
      (node (ref "JP4") (pin "2") (pinfunction "2_2") (pintype "passive"))
      (node (ref "R54") (pin "1") (pinfunction "1_1") (pintype "passive"))
      (node (ref "VD3") (pin "1") (pinfunction "A_1") (pintype "passive"))
    )
    (net (code "16") (name "/CP_SIG") (class "Default")
      (node (ref "R52") (pin "1") (pinfunction "1_1") (pintype "passive"))
      (node (ref "U1") (pin "20") (pinfunction "P3.7/INT3/TxD_2/CMP+_20") (pintype "passive"))
      (node (ref "U2") (pin "6") (pinfunction "S_6") (pintype "input"))
    )
    (net (code "17") (name "/DIN1") (class "Default")
      (node (ref "JP8") (pin "3") (pinfunction "3_3") (pintype "passive"))
      (node (ref "R81") (pin "2") (pinfunction "2_2") (pintype "passive"))
      (node (ref "R83") (pin "2") (pinfunction "2_2") (pintype "passive"))
    )
    (net (code "18") (name "/DIN2") (class "Default")
      (node (ref "JP8") (pin "2") (pinfunction "2_2") (pintype "passive"))
      (node (ref "R82") (pin "2") (pinfunction "2_2") (pintype "passive"))
      (node (ref "R84") (pin "2") (pinfunction "2_2") (pintype "passive"))
    )
    (net (code "19") (name "/DIN3") (class "Default")
      (node (ref "JP8") (pin "1") (pinfunction "1_1") (pintype "passive"))
      (node (ref "R86") (pin "2") (pinfunction "2_2") (pintype "passive"))
      (node (ref "R87") (pin "2") (pinfunction "2_2") (pintype "passive"))
    )
    (net (code "20") (name "/DIN_MCU") (class "Default")
      (node (ref "LED10") (pin "2") (pinfunction "K_2") (pintype "passive"))
      (node (ref "Q6") (pin "3") (pinfunction "C_3") (pintype "passive"))
      (node (ref "U1") (pin "27") (pinfunction "PWM4P_2/P2.6_27") (pintype "passive"))
    )
    (net (code "21") (name "/DIN_MCU2") (class "Default")
      (node (ref "LED11") (pin "2") (pinfunction "K_2") (pintype "passive"))
      (node (ref "Q7") (pin "3") (pinfunction "C_3") (pintype "passive"))
      (node (ref "U1") (pin "26") (pinfunction "PWM3N_2/I2CSCL_2/SCLK_2/P2.5_26") (pintype "passive"))
    )
    (net (code "22") (name "/DIN_MCU3") (class "Default")
      (node (ref "LED12") (pin "2") (pinfunction "K_2") (pintype "passive"))
      (node (ref "Q8") (pin "3") (pinfunction "C_3") (pintype "passive"))
      (node (ref "U1") (pin "25") (pinfunction "PWM3P_2/I2CSDA_2/MISO_2/P2.4_25") (pintype "passive"))
    )
    (net (code "23") (name "/DL_RXD") (class "Default")
      (node (ref "JP5") (pin "3") (pinfunction "3_3") (pintype "passive"))
      (node (ref "U1") (pin "13") (pinfunction "P3.0/RxD/INT4_13") (pintype "passive"))
    )
    (net (code "24") (name "/DL_TXD") (class "Default")
      (node (ref "JP5") (pin "4") (pinfunction "4_4") (pintype "passive"))
      (node (ref "U1") (pin "14") (pinfunction "P3.1/TxD_14") (pintype "passive"))
    )
    (net (code "25") (name "/EMG_OUT") (class "Default")
      (node (ref "R50") (pin "1") (pinfunction "1_1") (pintype "passive"))
      (node (ref "U1") (pin "16") (pinfunction "P3.3/INT1/MISO_4/I2CSDA_4/PWM4N_4/PWM7_2_16") (pintype "passive"))
      (node (ref "U3") (pin "4") (pinfunction "Y_4") (pintype "output"))
      (node (ref "U4") (pin "1") (pinfunction "A_1") (pintype "input"))
    )
    (net (code "26") (name "/EMG_STOP") (class "Default")
      (node (ref "C23") (pin "2") (pinfunction "2_2") (pintype "passive"))
      (node (ref "IC11") (pin "3") (pinfunction "E_3") (pintype "passive"))
      (node (ref "R60") (pin "2") (pinfunction "2_2") (pintype "passive"))
      (node (ref "U1") (pin "17") (pinfunction "P3.4/T0/T1CLKO/MOSI_4/PWM4P_4/PWM8_2/CMPO_17") (pintype "passive"))
      (node (ref "U3") (pin "2") (pinfunction "B_2") (pintype "input"))
    )
    (net (code "27") (name "/LED1") (class "Default")
      (node (ref "R70") (pin "2") (pinfunction "2_2") (pintype "passive"))
      (node (ref "R74") (pin "2") (pinfunction "2_2") (pintype "passive"))
      (node (ref "U1") (pin "24") (pinfunction "P2.3/MOSI_2/PWM2N_2/PWM8_24") (pintype "passive"))
    )
    (net (code "28") (name "/LED2") (class "Default")
      (node (ref "R71") (pin "2") (pinfunction "2_2") (pintype "passive"))
      (node (ref "R75") (pin "2") (pinfunction "2_2") (pintype "passive"))
      (node (ref "U1") (pin "23") (pinfunction "P2.2/SS_2/PWM2P_2/PWM7_23") (pintype "passive"))
    )
    (net (code "29") (name "/LED3") (class "Default")
      (node (ref "R72") (pin "2") (pinfunction "2_2") (pintype "passive"))
      (node (ref "R76") (pin "2") (pinfunction "2_2") (pintype "passive"))
      (node (ref "U1") (pin "22") (pinfunction "P2.1/PWM1N_2/PWM6_22") (pintype "passive"))
    )
    (net (code "30") (name "/LED4") (class "Default")
      (node (ref "R73") (pin "2") (pinfunction "2_2") (pintype "passive"))
      (node (ref "R77") (pin "2") (pinfunction "2_2") (pintype "passive"))
      (node (ref "U1") (pin "21") (pinfunction "P2.0/PWM1P_2/PWM5_21") (pintype "passive"))
    )
    (net (code "31") (name "/OUT_VOL") (class "Default")
      (node (ref "C18") (pin "2") (pinfunction "2_2") (pintype "passive"))
      (node (ref "IC5") (pin "3") (pinfunction "E_3") (pintype "passive"))
      (node (ref "R36") (pin "2") (pinfunction "2_2") (pintype "passive"))
      (node (ref "U1") (pin "30") (pinfunction "T3CLKO/PWM6_3/ADC9/P0.1_30") (pintype "passive"))
    )
    (net (code "32") (name "/RELAY_EN") (class "Default")
      (node (ref "U4") (pin "4") (pinfunction "Y_4") (pintype "output"))
    )
    (net (code "33") (name "/RELAY_OUT") (class "Default")
      (node (ref "U1") (pin "29") (pinfunction "T3/PWM5_3/ADC8/P0.0_29") (pintype "passive"))
      (node (ref "U4") (pin "2") (pinfunction "B_2") (pintype "input"))
    )
    (net (code "34") (name "/RST") (class "Default")
      (node (ref "C31") (pin "2") (pinfunction "2_2") (pintype "passive"))
      (node (ref "IC12") (pin "7") (pinfunction "~{RESET}_7") (pintype "passive"))
      (node (ref "JP5") (pin "2") (pinfunction "2_2") (pintype "passive"))
      (node (ref "R56") (pin "1") (pinfunction "1_1") (pintype "passive"))
      (node (ref "R61") (pin "1") (pinfunction "1_1") (pintype "passive"))
      (node (ref "SW1") (pin "2") (pinfunction "2_2") (pintype "passive"))
    )
    (net (code "35") (name "/ST_RXD") (class "Default")
      (node (ref "JP6") (pin "3") (pinfunction "3_3") (pintype "passive"))
      (node (ref "U1") (pin "1") (pinfunction "RxD2/PWM1P/ADC0/P1.0_1") (pintype "passive"))
    )
    (net (code "36") (name "/ST_TXD") (class "Default")
      (node (ref "JP6") (pin "4") (pinfunction "4_4") (pintype "passive"))
      (node (ref "U1") (pin "2") (pinfunction "TxD2/PWM1N/ADC1/P1.1_2") (pintype "passive"))
    )
    (net (code "37") (name "/SW_CP_SIG") (class "Default")
      (node (ref "IC6") (pin "6") (pinfunction "IN-_6") (pintype "input"))
      (node (ref "IC6") (pin "7") (pinfunction "OUT_7") (pintype "output"))
      (node (ref "R44") (pin "2") (pinfunction "2_2") (pintype "passive"))
      (node (ref "U1") (pin "32") (pinfunction "T4CLKO/PWM8_3//ADC11/P0.3_32") (pintype "passive"))
    )
    (net (code "38") (name "/TMP_ERR") (class "Default")
      (node (ref "C22") (pin "2") (pinfunction "2_2") (pintype "passive"))
      (node (ref "IC10") (pin "3") (pinfunction "E_3") (pintype "passive"))
      (node (ref "R55") (pin "2") (pinfunction "2_2") (pintype "passive"))
      (node (ref "U1") (pin "18") (pinfunction "P3.5/T1/T0CLKO/SS_4/PWMFLT/PWMFLT2_18") (pintype "passive"))
      (node (ref "U3") (pin "1") (pinfunction "A_1") (pintype "input"))
    )
    (net (code "39") (name "/V_N") (class "Default")
      (node (ref "C11") (pin "2") (pinfunction "2_2") (pintype "passive"))
      (node (ref "IC1") (pin "7") (pinfunction "VN_7") (pintype "passive"))
      (node (ref "J1") (pin "1") (pinfunction "A_1") (pintype "passive"))
      (node (ref "R12") (pin "2") (pinfunction "2_2") (pintype "passive"))
      (node (ref "R17") (pin "1") (pinfunction "1_1") (pintype "passive"))
    )
    (net (code "40") (name "/V_P") (class "Default")
      (node (ref "C14") (pin "2") (pinfunction "2_2") (pintype "passive"))
      (node (ref "IC1") (pin "6") (pinfunction "VP_6") (pintype "passive"))
      (node (ref "J1") (pin "2") (pinfunction "K_2") (pintype "passive"))
      (node (ref "R22") (pin "1") (pinfunction "1_1") (pintype "passive"))
      (node (ref "R23") (pin "2") (pinfunction "2_2") (pintype "passive"))
    )
    (net (code "41") (name "/WDG_FEED") (class "Default")
      (node (ref "IC12") (pin "6") (pinfunction "WDI_6") (pintype "passive"))
      (node (ref "U1") (pin "28") (pinfunction "PWM4N_2/P2.7_28") (pintype "passive"))
    )
    (net (code "42") (name "GND") (class "Default")
      (node (ref "*") (pin "0") (pinfunction "0_0") (pintype "passive"))
      (node (ref "*1") (pin "0") (pinfunction "0_0") (pintype "passive"))
      (node (ref "*2") (pin "0") (pinfunction "0_0") (pintype "passive"))
      (node (ref "*3") (pin "0") (pinfunction "0_0") (pintype "passive"))
      (node (ref "C1") (pin "1") (pinfunction "1_1") (pintype "passive"))
      (node (ref "C11") (pin "1") (pinfunction "1_1") (pintype "passive"))
      (node (ref "C12") (pin "1") (pinfunction "1_1") (pintype "passive"))
      (node (ref "C13") (pin "1") (pinfunction "1_1") (pintype "passive"))
      (node (ref "C14") (pin "1") (pinfunction "1_1") (pintype "passive"))
      (node (ref "C15") (pin "1") (pinfunction "1_1") (pintype "passive"))
      (node (ref "C16") (pin "1") (pinfunction "1_1") (pintype "passive"))
      (node (ref "C17") (pin "2") (pinfunction "2_2") (pintype "passive"))
      (node (ref "C18") (pin "1") (pinfunction "1_1") (pintype "passive"))
      (node (ref "C2") (pin "2") (pinfunction "2_2") (pintype "passive"))
      (node (ref "C20") (pin "1") (pinfunction "1_1") (pintype "passive"))
      (node (ref "C22") (pin "1") (pinfunction "1_1") (pintype "passive"))
      (node (ref "C23") (pin "1") (pinfunction "1_1") (pintype "passive"))
      (node (ref "C24") (pin "1") (pinfunction "1_1") (pintype "passive"))
      (node (ref "C25") (pin "1") (pinfunction "1_1") (pintype "passive"))
      (node (ref "C26") (pin "1") (pinfunction "1_1") (pintype "passive"))
      (node (ref "C27") (pin "1") (pinfunction "1_1") (pintype "passive"))
      (node (ref "C28") (pin "1") (pinfunction "1_1") (pintype "passive"))
      (node (ref "C29") (pin "1") (pinfunction "1_1") (pintype "passive"))
      (node (ref "C3") (pin "1") (pinfunction "1_1") (pintype "passive"))
      (node (ref "C30") (pin "1") (pinfunction "1_1") (pintype "passive"))
      (node (ref "C31") (pin "1") (pinfunction "1_1") (pintype "passive"))
      (node (ref "C39") (pin "1") (pinfunction "1_1") (pintype "passive"))
      (node (ref "C4") (pin "1") (pinfunction "1_1") (pintype "passive"))
      (node (ref "C40") (pin "1") (pinfunction "1_1") (pintype "passive"))
      (node (ref "C41") (pin "1") (pinfunction "1_1") (pintype "passive"))
      (node (ref "C42") (pin "1") (pinfunction "1_1") (pintype "passive"))
      (node (ref "C43") (pin "1") (pinfunction "1_1") (pintype "passive"))
      (node (ref "C44") (pin "1") (pinfunction "1_1") (pintype "passive"))
      (node (ref "C45") (pin "1") (pinfunction "1_1") (pintype "passive"))
      (node (ref "C46") (pin "1") (pinfunction "1_1") (pintype "passive"))
      (node (ref "C47") (pin "1") (pinfunction "1_1") (pintype "passive"))
      (node (ref "C48") (pin "1") (pinfunction "1_1") (pintype "passive"))
      (node (ref "C49") (pin "1") (pinfunction "1_1") (pintype "passive"))
      (node (ref "C5") (pin "1") (pinfunction "1_1") (pintype "passive"))
      (node (ref "C50") (pin "1") (pinfunction "1_1") (pintype "passive"))
      (node (ref "C51") (pin "1") (pinfunction "1_1") (pintype "passive"))
      (node (ref "C52") (pin "1") (pinfunction "1_1") (pintype "passive"))
      (node (ref "C53") (pin "1") (pinfunction "1_1") (pintype "passive"))
      (node (ref "C6") (pin "1") (pinfunction "1_1") (pintype "passive"))
      (node (ref "C7") (pin "1") (pinfunction "1_1") (pintype "passive"))
      (node (ref "C8") (pin "1") (pinfunction "1_1") (pintype "passive"))
      (node (ref "C9") (pin "2") (pinfunction "2_2") (pintype "passive"))
      (node (ref "DR1") (pin "2") (pinfunction "K_2") (pintype "passive"))
      (node (ref "IC1") (pin "10") (pinfunction "DGND_10") (pintype "passive"))
      (node (ref "IC1") (pin "9") (pinfunction "AGND_9") (pintype "passive"))
      (node (ref "IC12") (pin "3") (pinfunction "GND_3") (pintype "passive"))
      (node (ref "IC12") (pin "4") (pinfunction "PFI_4") (pintype "passive"))
      (node (ref "IC2") (pin "2") (pinfunction "K_2") (pintype "passive"))
      (node (ref "IC3") (pin "5") (pinfunction "IN+_5") (pintype "input"))
      (node (ref "IC3") (pin "6") (pinfunction "IN-_6") (pintype "input"))
      (node (ref "IC4") (pin "3") (pinfunction "IN+_3") (pintype "input"))
      (node (ref "IC9") (pin "3") (pinfunction "K_3") (pintype "passive"))
      (node (ref "JACIN") (pin "3") (pinfunction "3_3") (pintype "passive"))
      (node (ref "JDC1") (pin "2") (pinfunction "2_2") (pintype "passive"))
      (node (ref "JP5") (pin "1") (pinfunction "1_1") (pintype "passive"))
      (node (ref "JP6") (pin "1") (pinfunction "1_1") (pintype "passive"))
      (node (ref "JP7") (pin "1") (pinfunction "1_1") (pintype "passive"))
      (node (ref "JP7") (pin "2") (pinfunction "2_2") (pintype "passive"))
      (node (ref "JP8") (pin "4") (pinfunction "4_4") (pintype "passive"))
      (node (ref "J_TMP_SENSOR") (pin "1") (pinfunction "1_1") (pintype "passive"))
      (node (ref "J_TMP_SENSOR") (pin "3") (pinfunction "3_3") (pintype "passive"))
      (node (ref "J_TMP_SENSOR") (pin "5") (pinfunction "5_5") (pintype "passive"))
      (node (ref "J_TMP_SENSOR") (pin "7") (pinfunction "7_7") (pintype "passive"))
      (node (ref "LED2") (pin "2") (pinfunction "K_2") (pintype "passive"))
      (node (ref "LED3") (pin "2") (pinfunction "K_2") (pintype "passive"))
      (node (ref "LED4") (pin "2") (pinfunction "K_2") (pintype "passive"))
      (node (ref "LED5") (pin "2") (pinfunction "K_2") (pintype "passive"))
      (node (ref "Q2") (pin "2") (pinfunction "E_2") (pintype "passive"))
      (node (ref "Q3") (pin "2") (pinfunction "E_2") (pintype "passive"))
      (node (ref "Q4") (pin "2") (pinfunction "E_2") (pintype "passive"))
      (node (ref "Q5") (pin "2") (pinfunction "E_2") (pintype "passive"))
      (node (ref "Q6") (pin "2") (pinfunction "E_2") (pintype "passive"))
      (node (ref "Q7") (pin "2") (pinfunction "E_2") (pintype "passive"))
      (node (ref "Q8") (pin "2") (pinfunction "E_2") (pintype "passive"))
      (node (ref "R10") (pin "2") (pinfunction "2_2") (pintype "passive"))
      (node (ref "R12") (pin "1") (pinfunction "1_1") (pintype "passive"))
      (node (ref "R2") (pin "1") (pinfunction "1_1") (pintype "passive"))
      (node (ref "R23") (pin "1") (pinfunction "1_1") (pintype "passive"))
      (node (ref "R3") (pin "2") (pinfunction "2_2") (pintype "passive"))
      (node (ref "R36") (pin "1") (pinfunction "1_1") (pintype "passive"))
      (node (ref "R42") (pin "1") (pinfunction "1_1") (pintype "passive"))
      (node (ref "R44") (pin "1") (pinfunction "1_1") (pintype "passive"))
      (node (ref "R50") (pin "2") (pinfunction "2_2") (pintype "passive"))
      (node (ref "R55") (pin "1") (pinfunction "1_1") (pintype "passive"))
      (node (ref "R60") (pin "1") (pinfunction "1_1") (pintype "passive"))
      (node (ref "R74") (pin "1") (pinfunction "1_1") (pintype "passive"))
      (node (ref "R75") (pin "1") (pinfunction "1_1") (pintype "passive"))
      (node (ref "R76") (pin "1") (pinfunction "1_1") (pintype "passive"))
      (node (ref "R77") (pin "1") (pinfunction "1_1") (pintype "passive"))
      (node (ref "R8") (pin "1") (pinfunction "1_1") (pintype "passive"))
      (node (ref "R83") (pin "1") (pinfunction "1_1") (pintype "passive"))
      (node (ref "R84") (pin "1") (pinfunction "1_1") (pintype "passive"))
      (node (ref "R87") (pin "1") (pinfunction "1_1") (pintype "passive"))
      (node (ref "SW1") (pin "1") (pinfunction "1_1") (pintype "passive"))
      (node (ref "U1") (pin "12") (pinfunction "Gnd/AGnd_12") (pintype "passive"))
      (node (ref "U2") (pin "2") (pinfunction "GND_2") (pintype "power_in"))
      (node (ref "U3") (pin "3") (pinfunction "GND_3") (pintype "power_in"))
      (node (ref "U4") (pin "3") (pinfunction "GND_3") (pintype "power_in"))
      (node (ref "V1") (pin "2") (pinfunction "GND_2") (pintype "passive"))
      (node (ref "V2") (pin "1") (pinfunction "GND_1") (pintype "passive"))
      (node (ref "VD1") (pin "1") (pinfunction "A_1") (pintype "passive"))
      (node (ref "X1") (pin "2") (pinfunction "2_2") (pintype "passive"))
      (node (ref "X1") (pin "4") (pinfunction "4_4") (pintype "passive"))
    )
    (net (code "43") (name "Net-(IC1-AT0)") (class "Default")
      (node (ref "IC1") (pin "11") (pinfunction "AT0_11") (pintype "passive"))
      (node (ref "R24") (pin "2") (pinfunction "2_2") (pintype "passive"))
    )
    (net (code "44") (name "Net-(IC1-AT1)") (class "Default")
      (node (ref "IC1") (pin "12") (pinfunction "AT1_12") (pintype "passive"))
      (node (ref "R25") (pin "2") (pinfunction "2_2") (pintype "passive"))
    )
    (net (code "45") (name "Net-(IC1-AT2)") (class "Default")
      (node (ref "IC1") (pin "13") (pinfunction "AT2_13") (pintype "passive"))
      (node (ref "R26") (pin "2") (pinfunction "2_2") (pintype "passive"))
    )
    (net (code "46") (name "Net-(IC1-AT3)") (class "Default")
      (node (ref "IC1") (pin "14") (pinfunction "AT3_14") (pintype "passive"))
      (node (ref "R27") (pin "2") (pinfunction "2_2") (pintype "passive"))
    )
    (net (code "47") (name "Net-(IC1-AVDD)") (class "Default")
      (node (ref "C3") (pin "2") (pinfunction "2_2") (pintype "passive"))
      (node (ref "C4") (pin "2") (pinfunction "2_2") (pintype "passive"))
      (node (ref "IC1") (pin "1") (pinfunction "AVDD_1") (pintype "passive"))
      (node (ref "R4") (pin "1") (pinfunction "1_1") (pintype "passive"))
    )
    (net (code "48") (name "Net-(IC1-CF)") (class "Default")
      (node (ref "IC1") (pin "22") (pinfunction "CF_22") (pintype "passive"))
      (node (ref "R9") (pin "1") (pinfunction "1_1") (pintype "passive"))
    )
    (net (code "49") (name "Net-(IC1-CLKIN)") (class "Default")
      (node (ref "C15") (pin "2") (pinfunction "2_2") (pintype "passive"))
      (node (ref "IC1") (pin "16") (pinfunction "CLKIN_16") (pintype "passive"))
      (node (ref "X1") (pin "1") (pinfunction "1_1") (pintype "passive"))
    )
    (net (code "50") (name "Net-(IC1-CLKOUT)") (class "Default")
      (node (ref "C16") (pin "2") (pinfunction "2_2") (pintype "passive"))
      (node (ref "IC1") (pin "17") (pinfunction "CLKOUT_17") (pintype "passive"))
      (node (ref "X1") (pin "3") (pinfunction "3_3") (pintype "passive"))
    )
    (net (code "51") (name "Net-(IC1-VREF)") (class "Default")
      (node (ref "C12") (pin "2") (pinfunction "2_2") (pintype "passive"))
      (node (ref "C13") (pin "2") (pinfunction "2_2") (pintype "passive"))
      (node (ref "IC1") (pin "8") (pinfunction "VREF_8") (pintype "passive"))
    )
    (net (code "52") (name "Net-(IC1-{slash}RST)") (class "Default")
      (node (ref "C7") (pin "2") (pinfunction "2_2") (pintype "passive"))
      (node (ref "IC1") (pin "23") (pinfunction "/RST_23") (pintype "passive"))
      (node (ref "R6") (pin "1") (pinfunction "1_1") (pintype "passive"))
    )
    (net (code "53") (name "Net-(IC2-A)") (class "Default")
      (node (ref "IC2") (pin "1") (pinfunction "A_1") (pintype "passive"))
      (node (ref "LED1") (pin "2") (pinfunction "K_2") (pintype "passive"))
    )
    (net (code "54") (name "Net-(IC2-C)") (class "Default")
      (node (ref "C10") (pin "2") (pinfunction "2_2") (pintype "passive"))
      (node (ref "IC2") (pin "4") (pinfunction "C_4") (pintype "passive"))
      (node (ref "JP3") (pin "2") (pinfunction "2_2") (pintype "passive"))
    )
    (net (code "55") (name "Net-(IC2-E)") (class "Default")
      (node (ref "C10") (pin "1") (pinfunction "1_1") (pintype "passive"))
      (node (ref "IC2") (pin "3") (pinfunction "E_3") (pintype "passive"))
      (node (ref "JP3") (pin "1") (pinfunction "1_1") (pintype "passive"))
    )
    (net (code "56") (name "Net-(IC3A-IN+)") (class "Default")
      (node (ref "C19") (pin "1") (pinfunction "1_1") (pintype "passive"))
      (node (ref "IC3") (pin "3") (pinfunction "IN+_3") (pintype "input"))
      (node (ref "IC4") (pin "1") (pinfunction "OUT_1") (pintype "output"))
      (node (ref "R28") (pin "1") (pinfunction "1_1") (pintype "passive"))
      (node (ref "R37") (pin "2") (pinfunction "2_2") (pintype "passive"))
      (node (ref "VD1") (pin "2") (pinfunction "K_2") (pintype "passive"))
    )
    (net (code "57") (name "Net-(IC3A-IN-)") (class "Default")
      (node (ref "IC3") (pin "2") (pinfunction "IN-_2") (pintype "input"))
      (node (ref "R31") (pin "2") (pinfunction "2_2") (pintype "passive"))
    )
    (net (code "58") (name "Net-(IC3A-OUT)") (class "Default")
      (node (ref "IC3") (pin "1") (pinfunction "OUT_1") (pintype "output"))
      (node (ref "R30") (pin "1") (pinfunction "1_1") (pintype "passive"))
    )
    (net (code "59") (name "Net-(IC4A-IN-)") (class "Default")
      (node (ref "C19") (pin "2") (pinfunction "2_2") (pintype "passive"))
      (node (ref "IC4") (pin "2") (pinfunction "IN-_2") (pintype "input"))
      (node (ref "R30") (pin "2") (pinfunction "2_2") (pintype "passive"))
      (node (ref "R37") (pin "1") (pinfunction "1_1") (pintype "passive"))
    )
    (net (code "60") (name "Net-(IC4B-IN+)") (class "Default")
      (node (ref "C17") (pin "1") (pinfunction "1_1") (pintype "passive"))
      (node (ref "IC4") (pin "5") (pinfunction "IN+_5") (pintype "input"))
      (node (ref "R28") (pin "2") (pinfunction "2_2") (pintype "passive"))
    )
    (net (code "61") (name "Net-(IC5-A)") (class "Default")
      (node (ref "IC5") (pin "1") (pinfunction "A_1") (pintype "passive"))
      (node (ref "R35") (pin "2") (pinfunction "2_2") (pintype "passive"))
      (node (ref "VD2") (pin "2") (pinfunction "K_2") (pintype "passive"))
    )
    (net (code "62") (name "Net-(IC5-C)") (class "Default")
      (node (ref "IC5") (pin "4") (pinfunction "C_4") (pintype "passive"))
      (node (ref "R29") (pin "1") (pinfunction "1_1") (pintype "passive"))
    )
    (net (code "63") (name "Net-(IC6A-IN+)") (class "Default")
      (node (ref "IC6") (pin "3") (pinfunction "IN+_3") (pintype "input"))
      (node (ref "R38") (pin "1") (pinfunction "1_1") (pintype "passive"))
      (node (ref "R42") (pin "2") (pinfunction "2_2") (pintype "passive"))
    )
    (net (code "64") (name "Net-(IC6A-IN-)") (class "Default")
      (node (ref "IC6") (pin "1") (pinfunction "OUT_1") (pintype "output"))
      (node (ref "IC6") (pin "2") (pinfunction "IN-_2") (pintype "input"))
      (node (ref "R31") (pin "1") (pinfunction "1_1") (pintype "passive"))
      (node (ref "R40") (pin "1") (pinfunction "1_1") (pintype "passive"))
    )
    (net (code "65") (name "Net-(IC6B-IN+)") (class "Default")
      (node (ref "C20") (pin "2") (pinfunction "2_2") (pintype "passive"))
      (node (ref "IC6") (pin "5") (pinfunction "IN+_5") (pintype "input"))
      (node (ref "R39") (pin "2") (pinfunction "2_2") (pintype "passive"))
      (node (ref "R41") (pin "2") (pinfunction "2_2") (pintype "passive"))
    )
    (net (code "66") (name "Net-(IC9-A)") (class "Default")
      (node (ref "IC9") (pin "1") (pinfunction "A_1") (pintype "passive"))
      (node (ref "R52") (pin "2") (pinfunction "2_2") (pintype "passive"))
    )
    (net (code "67") (name "Net-(IC9-OUT)") (class "Default")
      (node (ref "IC9") (pin "5") (pinfunction "OUT_5") (pintype "passive"))
      (node (ref "R54") (pin "2") (pinfunction "2_2") (pintype "passive"))
    )
    (net (code "68") (name "Net-(IC10-A)") (class "Default")
      (node (ref "IC10") (pin "1") (pinfunction "A_1") (pintype "passive"))
      (node (ref "R53") (pin "1") (pinfunction "1_1") (pintype "passive"))
    )
    (net (code "69") (name "Net-(IC10-C)") (class "Default")
      (node (ref "IC10") (pin "4") (pinfunction "C_4") (pintype "passive"))
      (node (ref "R51") (pin "1") (pinfunction "1_1") (pintype "passive"))
    )
    (net (code "70") (name "Net-(IC10-K)") (class "Default")
      (node (ref "IC10") (pin "2") (pinfunction "K_2") (pintype "passive"))
      (node (ref "J_TMP_SENSOR") (pin "4") (pinfunction "4_4") (pintype "passive"))
      (node (ref "J_TMP_SENSOR") (pin "6") (pinfunction "6_6") (pintype "passive"))
      (node (ref "J_TMP_SENSOR") (pin "8") (pinfunction "8_8") (pintype "passive"))
    )
    (net (code "71") (name "Net-(IC11-A)") (class "Default")
      (node (ref "IC11") (pin "1") (pinfunction "A_1") (pintype "passive"))
      (node (ref "R58") (pin "1") (pinfunction "1_1") (pintype "passive"))
    )
    (net (code "72") (name "Net-(IC11-C)") (class "Default")
      (node (ref "IC11") (pin "4") (pinfunction "C_4") (pintype "passive"))
      (node (ref "R57") (pin "1") (pinfunction "1_1") (pintype "passive"))
    )
    (net (code "73") (name "Net-(IC11-K)") (class "Default")
      (node (ref "IC11") (pin "2") (pinfunction "K_2") (pintype "passive"))
      (node (ref "J_TMP_SENSOR") (pin "2") (pinfunction "2_2") (pintype "passive"))
    )
    (net (code "74") (name "Net-(IC12-~{MR})") (class "Default")
      (node (ref "IC12") (pin "1") (pinfunction "~{MR}_1") (pintype "passive"))
      (node (ref "IC12") (pin "8") (pinfunction "~{WDO}_8") (pintype "passive"))
    )
    (net (code "75") (name "Net-(J1-C)") (class "Default")
      (node (ref "J1") (pin "4") (pinfunction "C_4") (pintype "passive"))
      (node (ref "R21") (pin "2") (pinfunction "2_2") (pintype "passive"))
    )
    (net (code "76") (name "Net-(J1-E)") (class "Default")
      (node (ref "J1") (pin "3") (pinfunction "E_3") (pintype "passive"))
      (node (ref "R16") (pin "2") (pinfunction "2_2") (pintype "passive"))
    )
    (net (code "77") (name "Net-(JP1-Pad1)") (class "Default")
      (node (ref "JP1") (pin "1") (pinfunction "1_1") (pintype "passive"))
      (node (ref "R3") (pin "1") (pinfunction "1_1") (pintype "passive"))
      (node (ref "R5") (pin "1") (pinfunction "1_1") (pintype "passive"))
    )
    (net (code "78") (name "Net-(JP1-Pad2)") (class "Default")
      (node (ref "JP1") (pin "2") (pinfunction "2_2") (pintype "passive"))
      (node (ref "R1") (pin "1") (pinfunction "1_1") (pintype "passive"))
      (node (ref "R2") (pin "2") (pinfunction "2_2") (pintype "passive"))
    )
    (net (code "79") (name "Net-(JP2-Pad1)") (class "Default")
      (node (ref "JP2") (pin "1") (pinfunction "1_1") (pintype "passive"))
      (node (ref "R10") (pin "1") (pinfunction "1_1") (pintype "passive"))
      (node (ref "R11") (pin "1") (pinfunction "1_1") (pintype "passive"))
    )
    (net (code "80") (name "Net-(JP2-Pad2)") (class "Default")
      (node (ref "JP2") (pin "2") (pinfunction "2_2") (pintype "passive"))
      (node (ref "R7") (pin "1") (pinfunction "1_1") (pintype "passive"))
      (node (ref "R8") (pin "2") (pinfunction "2_2") (pintype "passive"))
    )
    (net (code "81") (name "Net-(LED1-A)") (class "Default")
      (node (ref "LED1") (pin "1") (pinfunction "A_1") (pintype "passive"))
      (node (ref "R9") (pin "2") (pinfunction "2_2") (pintype "passive"))
    )
    (net (code "82") (name "Net-(LED2-A)") (class "Default")
      (node (ref "LED2") (pin "1") (pinfunction "A_1") (pintype "passive"))
      (node (ref "R24") (pin "1") (pinfunction "1_1") (pintype "passive"))
    )
    (net (code "83") (name "Net-(LED3-A)") (class "Default")
      (node (ref "LED3") (pin "1") (pinfunction "A_1") (pintype "passive"))
      (node (ref "R25") (pin "1") (pinfunction "1_1") (pintype "passive"))
    )
    (net (code "84") (name "Net-(LED4-A)") (class "Default")
      (node (ref "LED4") (pin "1") (pinfunction "A_1") (pintype "passive"))
      (node (ref "R26") (pin "1") (pinfunction "1_1") (pintype "passive"))
    )
    (net (code "85") (name "Net-(LED5-A)") (class "Default")
      (node (ref "LED5") (pin "1") (pinfunction "A_1") (pintype "passive"))
      (node (ref "R27") (pin "1") (pinfunction "1_1") (pintype "passive"))
    )
    (net (code "86") (name "Net-(LED6-A)") (class "Default")
      (node (ref "LED6") (pin "1") (pinfunction "A_1") (pintype "passive"))
      (node (ref "R63") (pin "1") (pinfunction "1_1") (pintype "passive"))
    )
    (net (code "87") (name "Net-(LED6-K)") (class "Default")
      (node (ref "LED6") (pin "2") (pinfunction "K_2") (pintype "passive"))
      (node (ref "Q2") (pin "3") (pinfunction "C_3") (pintype "passive"))
    )
    (net (code "88") (name "Net-(LED7-A)") (class "Default")
      (node (ref "LED7") (pin "1") (pinfunction "A_1") (pintype "passive"))
      (node (ref "R64") (pin "1") (pinfunction "1_1") (pintype "passive"))
    )
    (net (code "89") (name "Net-(LED7-K)") (class "Default")
      (node (ref "LED7") (pin "2") (pinfunction "K_2") (pintype "passive"))
      (node (ref "Q3") (pin "3") (pinfunction "C_3") (pintype "passive"))
    )
    (net (code "90") (name "Net-(LED8-A)") (class "Default")
      (node (ref "LED8") (pin "1") (pinfunction "A_1") (pintype "passive"))
      (node (ref "R65") (pin "1") (pinfunction "1_1") (pintype "passive"))
    )
    (net (code "91") (name "Net-(LED8-K)") (class "Default")
      (node (ref "LED8") (pin "2") (pinfunction "K_2") (pintype "passive"))
      (node (ref "Q4") (pin "3") (pinfunction "C_3") (pintype "passive"))
    )
    (net (code "92") (name "Net-(LED9-A)") (class "Default")
      (node (ref "LED9") (pin "1") (pinfunction "A_1") (pintype "passive"))
      (node (ref "R66") (pin "1") (pinfunction "1_1") (pintype "passive"))
    )
    (net (code "93") (name "Net-(LED9-K)") (class "Default")
      (node (ref "LED9") (pin "2") (pinfunction "K_2") (pintype "passive"))
      (node (ref "Q5") (pin "3") (pinfunction "C_3") (pintype "passive"))
    )
    (net (code "94") (name "Net-(LED10-A)") (class "Default")
      (node (ref "LED10") (pin "1") (pinfunction "A_1") (pintype "passive"))
      (node (ref "R79") (pin "1") (pinfunction "1_1") (pintype "passive"))
    )
    (net (code "95") (name "Net-(LED11-A)") (class "Default")
      (node (ref "LED11") (pin "1") (pinfunction "A_1") (pintype "passive"))
      (node (ref "R80") (pin "1") (pinfunction "1_1") (pintype "passive"))
    )
    (net (code "96") (name "Net-(LED12-A)") (class "Default")
      (node (ref "LED12") (pin "1") (pinfunction "A_1") (pintype "passive"))
      (node (ref "R85") (pin "1") (pinfunction "1_1") (pintype "passive"))
    )
    (net (code "97") (name "Net-(Q2-B)") (class "Default")
      (node (ref "C39") (pin "2") (pinfunction "2_2") (pintype "passive"))
      (node (ref "Q2") (pin "1") (pinfunction "B_1") (pintype "passive"))
      (node (ref "R70") (pin "1") (pinfunction "1_1") (pintype "passive"))
    )
    (net (code "98") (name "Net-(Q3-B)") (class "Default")
      (node (ref "C40") (pin "2") (pinfunction "2_2") (pintype "passive"))
      (node (ref "Q3") (pin "1") (pinfunction "B_1") (pintype "passive"))
      (node (ref "R71") (pin "1") (pinfunction "1_1") (pintype "passive"))
    )
    (net (code "99") (name "Net-(Q4-B)") (class "Default")
      (node (ref "C41") (pin "2") (pinfunction "2_2") (pintype "passive"))
      (node (ref "Q4") (pin "1") (pinfunction "B_1") (pintype "passive"))
      (node (ref "R72") (pin "1") (pinfunction "1_1") (pintype "passive"))
    )
    (net (code "100") (name "Net-(Q5-B)") (class "Default")
      (node (ref "C42") (pin "2") (pinfunction "2_2") (pintype "passive"))
      (node (ref "Q5") (pin "1") (pinfunction "B_1") (pintype "passive"))
      (node (ref "R73") (pin "1") (pinfunction "1_1") (pintype "passive"))
    )
    (net (code "101") (name "Net-(Q6-B)") (class "Default")
      (node (ref "C51") (pin "2") (pinfunction "2_2") (pintype "passive"))
      (node (ref "Q6") (pin "1") (pinfunction "B_1") (pintype "passive"))
      (node (ref "R81") (pin "1") (pinfunction "1_1") (pintype "passive"))
    )
    (net (code "102") (name "Net-(Q7-B)") (class "Default")
      (node (ref "C52") (pin "2") (pinfunction "2_2") (pintype "passive"))
      (node (ref "Q7") (pin "1") (pinfunction "B_1") (pintype "passive"))
      (node (ref "R82") (pin "1") (pinfunction "1_1") (pintype "passive"))
    )
    (net (code "103") (name "Net-(Q8-B)") (class "Default")
      (node (ref "C53") (pin "2") (pinfunction "2_2") (pintype "passive"))
      (node (ref "Q8") (pin "1") (pinfunction "B_1") (pintype "passive"))
      (node (ref "R86") (pin "1") (pinfunction "1_1") (pintype "passive"))
    )
    (net (code "104") (name "Net-(R13-Pad2)") (class "Default")
      (node (ref "R13") (pin "2") (pinfunction "2_2") (pintype "passive"))
      (node (ref "R14") (pin "1") (pinfunction "1_1") (pintype "passive"))
    )
    (net (code "105") (name "Net-(R14-Pad2)") (class "Default")
      (node (ref "R14") (pin "2") (pinfunction "2_2") (pintype "passive"))
      (node (ref "R15") (pin "1") (pinfunction "1_1") (pintype "passive"))
    )
    (net (code "106") (name "Net-(R15-Pad2)") (class "Default")
      (node (ref "R15") (pin "2") (pinfunction "2_2") (pintype "passive"))
      (node (ref "R16") (pin "1") (pinfunction "1_1") (pintype "passive"))
    )
    (net (code "107") (name "Net-(R17-Pad2)") (class "Default")
      (node (ref "R17") (pin "2") (pinfunction "2_2") (pintype "passive"))
      (node (ref "R22") (pin "2") (pinfunction "2_2") (pintype "passive"))
    )
    (net (code "108") (name "Net-(R18-Pad2)") (class "Default")
      (node (ref "R18") (pin "2") (pinfunction "2_2") (pintype "passive"))
      (node (ref "R19") (pin "1") (pinfunction "1_1") (pintype "passive"))
    )
    (net (code "109") (name "Net-(R19-Pad2)") (class "Default")
      (node (ref "R19") (pin "2") (pinfunction "2_2") (pintype "passive"))
      (node (ref "R20") (pin "1") (pinfunction "1_1") (pintype "passive"))
    )
    (net (code "110") (name "Net-(R20-Pad2)") (class "Default")
      (node (ref "R20") (pin "2") (pinfunction "2_2") (pintype "passive"))
      (node (ref "R21") (pin "1") (pinfunction "1_1") (pintype "passive"))
    )
    (net (code "111") (name "Net-(R32-Pad2)") (class "Default")
      (node (ref "R32") (pin "2") (pinfunction "2_2") (pintype "passive"))
      (node (ref "R33") (pin "1") (pinfunction "1_1") (pintype "passive"))
    )
    (net (code "112") (name "Net-(R33-Pad2)") (class "Default")
      (node (ref "R33") (pin "2") (pinfunction "2_2") (pintype "passive"))
      (node (ref "R34") (pin "1") (pinfunction "1_1") (pintype "passive"))
    )
    (net (code "113") (name "Net-(R34-Pad2)") (class "Default")
      (node (ref "R34") (pin "2") (pinfunction "2_2") (pintype "passive"))
      (node (ref "R35") (pin "1") (pinfunction "1_1") (pintype "passive"))
    )
    (net (code "114") (name "Net-(U1-P3.2{slash}INT0{slash}SCLK_4{slash}I2CSCL_4{slash}PWMETI{slash}PWMETI2)") (class "Default")
      (node (ref "R59") (pin "2") (pinfunction "2_2") (pintype "passive"))
      (node (ref "U1") (pin "15") (pinfunction "P3.2/INT0/SCLK_4/I2CSCL_4/PWMETI/PWMETI2_15") (pintype "passive"))
    )
    (net (code "115") (name "Net-(U1-P5.4{slash}RST{slash}MCLKO{slash}PWM6_2)") (class "Default")
      (node (ref "R56") (pin "2") (pinfunction "2_2") (pintype "passive"))
      (node (ref "U1") (pin "9") (pinfunction "P5.4/RST/MCLKO/PWM6_2_9") (pintype "passive"))
    )
    (net (code "116") (name "Net-(U2-A)") (class "Default")
      (node (ref "R40") (pin "2") (pinfunction "2_2") (pintype "passive"))
      (node (ref "U2") (pin "4") (pinfunction "A_4") (pintype "passive"))
    )
    (net (code "117") (name "Net-(U2-B1)") (class "Default")
      (node (ref "R39") (pin "1") (pinfunction "1_1") (pintype "passive"))
      (node (ref "U2") (pin "3") (pinfunction "B1_3") (pintype "passive"))
    )
    (net (code "118") (name "Net-(U2-B2)") (class "Default")
      (node (ref "R41") (pin "1") (pinfunction "1_1") (pintype "passive"))
      (node (ref "U2") (pin "1") (pinfunction "B2_1") (pintype "passive"))
    )
    (net (code "119") (name "Net-(VD3-K)") (class "Default")
      (node (ref "R38") (pin "2") (pinfunction "2_2") (pintype "passive"))
      (node (ref "VD3") (pin "2") (pinfunction "K_2") (pintype "passive"))
    )
    (net (code "120") (name "VCC-5V") (class "Default")
      (node (ref "C49") (pin "2") (pinfunction "2_2") (pintype "passive"))
      (node (ref "C50") (pin "2") (pinfunction "2_2") (pintype "passive"))
      (node (ref "IC3") (pin "4") (pinfunction "V-_4") (pintype "power_in"))
      (node (ref "IC4") (pin "4") (pinfunction "V-_4") (pintype "power_in"))
      (node (ref "IC6") (pin "4") (pinfunction "V-_4") (pintype "power_in"))
      (node (ref "V2") (pin "3") (pinfunction "Vout_3") (pintype "passive"))
    )
    (net (code "121") (name "VCC-12V") (class "Default")
      (node (ref "C47") (pin "2") (pinfunction "2_2") (pintype "passive"))
      (node (ref "C48") (pin "2") (pinfunction "2_2") (pintype "passive"))
      (node (ref "IC9") (pin "4") (pinfunction "VSS_4") (pintype "passive"))
      (node (ref "JDC1") (pin "3") (pinfunction "3_3") (pintype "passive"))
      (node (ref "V2") (pin "2") (pinfunction "Vin_2") (pintype "passive"))
    )
    (net (code "122") (name "VCC5V") (class "Default")
      (node (ref "C24") (pin "2") (pinfunction "2_2") (pintype "passive"))
      (node (ref "C25") (pin "2") (pinfunction "2_2") (pintype "passive"))
      (node (ref "C26") (pin "2") (pinfunction "2_2") (pintype "passive"))
      (node (ref "C27") (pin "2") (pinfunction "2_2") (pintype "passive"))
      (node (ref "C28") (pin "2") (pinfunction "2_2") (pintype "passive"))
      (node (ref "C30") (pin "2") (pinfunction "2_2") (pintype "passive"))
      (node (ref "C45") (pin "2") (pinfunction "2_2") (pintype "passive"))
      (node (ref "C46") (pin "2") (pinfunction "2_2") (pintype "passive"))
      (node (ref "C5") (pin "2") (pinfunction "2_2") (pintype "passive"))
      (node (ref "C6") (pin "2") (pinfunction "2_2") (pintype "passive"))
      (node (ref "IC1") (pin "24") (pinfunction "DVDD_24") (pintype "passive"))
      (node (ref "IC12") (pin "2") (pinfunction "VCC_2") (pintype "passive"))
      (node (ref "IC3") (pin "8") (pinfunction "V+_8") (pintype "power_in"))
      (node (ref "IC4") (pin "8") (pinfunction "V+_8") (pintype "power_in"))
      (node (ref "IC6") (pin "8") (pinfunction "V+_8") (pintype "power_in"))
      (node (ref "R29") (pin "2") (pinfunction "2_2") (pintype "passive"))
      (node (ref "R4") (pin "2") (pinfunction "2_2") (pintype "passive"))
      (node (ref "R51") (pin "2") (pinfunction "2_2") (pintype "passive"))
      (node (ref "R57") (pin "2") (pinfunction "2_2") (pintype "passive"))
      (node (ref "R59") (pin "1") (pinfunction "1_1") (pintype "passive"))
      (node (ref "R6") (pin "2") (pinfunction "2_2") (pintype "passive"))
      (node (ref "R61") (pin "2") (pinfunction "2_2") (pintype "passive"))
      (node (ref "R63") (pin "2") (pinfunction "2_2") (pintype "passive"))
      (node (ref "R64") (pin "2") (pinfunction "2_2") (pintype "passive"))
      (node (ref "R65") (pin "2") (pinfunction "2_2") (pintype "passive"))
      (node (ref "R66") (pin "2") (pinfunction "2_2") (pintype "passive"))
      (node (ref "R79") (pin "2") (pinfunction "2_2") (pintype "passive"))
      (node (ref "R80") (pin "2") (pinfunction "2_2") (pintype "passive"))
      (node (ref "R85") (pin "2") (pinfunction "2_2") (pintype "passive"))
      (node (ref "U1") (pin "10") (pinfunction "Vcc/AVcc_10") (pintype "passive"))
      (node (ref "U1") (pin "11") (pinfunction "ADC_VRef+_11") (pintype "passive"))
      (node (ref "U2") (pin "5") (pinfunction "VCC_5") (pintype "power_in"))
      (node (ref "U3") (pin "5") (pinfunction "VCC_5") (pintype "power_in"))
      (node (ref "U4") (pin "5") (pinfunction "VCC_5") (pintype "power_in"))
      (node (ref "V1") (pin "3") (pinfunction "Vout_3") (pintype "passive"))
    )
    (net (code "123") (name "VCC12V") (class "Default")
      (node (ref "C43") (pin "2") (pinfunction "2_2") (pintype "passive"))
      (node (ref "C44") (pin "2") (pinfunction "2_2") (pintype "passive"))
      (node (ref "IC9") (pin "6") (pinfunction "VDD_6") (pintype "passive"))
      (node (ref "JDC1") (pin "1") (pinfunction "1_1") (pintype "passive"))
      (node (ref "JP7") (pin "3") (pinfunction "3_3") (pintype "passive"))
      (node (ref "JP7") (pin "4") (pinfunction "4_4") (pintype "passive"))
      (node (ref "R53") (pin "2") (pinfunction "2_2") (pintype "passive"))
      (node (ref "R58") (pin "2") (pinfunction "2_2") (pintype "passive"))
      (node (ref "V1") (pin "1") (pinfunction "Vin_1") (pintype "passive"))
    )
    (net (code "124") (name "unconnected-(IC3B-OUT-Pad7)") (class "Default")
      (node (ref "IC3") (pin "7") (pinfunction "OUT_7") (pintype "output"))
    )
    (net (code "125") (name "unconnected-(IC9-NC-Pad2)") (class "Default")
      (node (ref "IC9") (pin "2") (pinfunction "NC_2") (pintype "passive"))
    )
    (net (code "126") (name "unconnected-(IC12-~{PFO}-Pad5)") (class "Default")
      (node (ref "IC12") (pin "5") (pinfunction "~{PFO}_5") (pintype "passive"))
    )
    (net (code "127") (name "unconnected-(JP6-Pad2)") (class "Default")
      (node (ref "JP6") (pin "2") (pinfunction "2_2") (pintype "passive"))
    )
    (net (code "128") (name "unconnected-(U1-XTALI{slash}TxD_3{slash}PWM5_2{slash}PWM4N{slash}ADC7{slash}P1.7-Pad8)") (class "Default")
      (node (ref "U1") (pin "8") (pinfunction "XTALI/TxD_3/PWM5_2/PWM4N/ADC7/P1.7_8") (pintype "passive"))
    )
    (net (code "129") (name "unconnected-(U1-XTALO{slash}MCLKO_2{slash}RxD_3{slash}PWM4P{slash}ADC6{slash}P1.6-Pad7)") (class "Default")
      (node (ref "U1") (pin "7") (pinfunction "XTALO/MCLKO_2/RxD_3/PWM4P/ADC6/P1.6_7") (pintype "passive"))
    )
  )
)
